# DRS4.net
KiCad netlist of a schematic drawn in Altium Designer
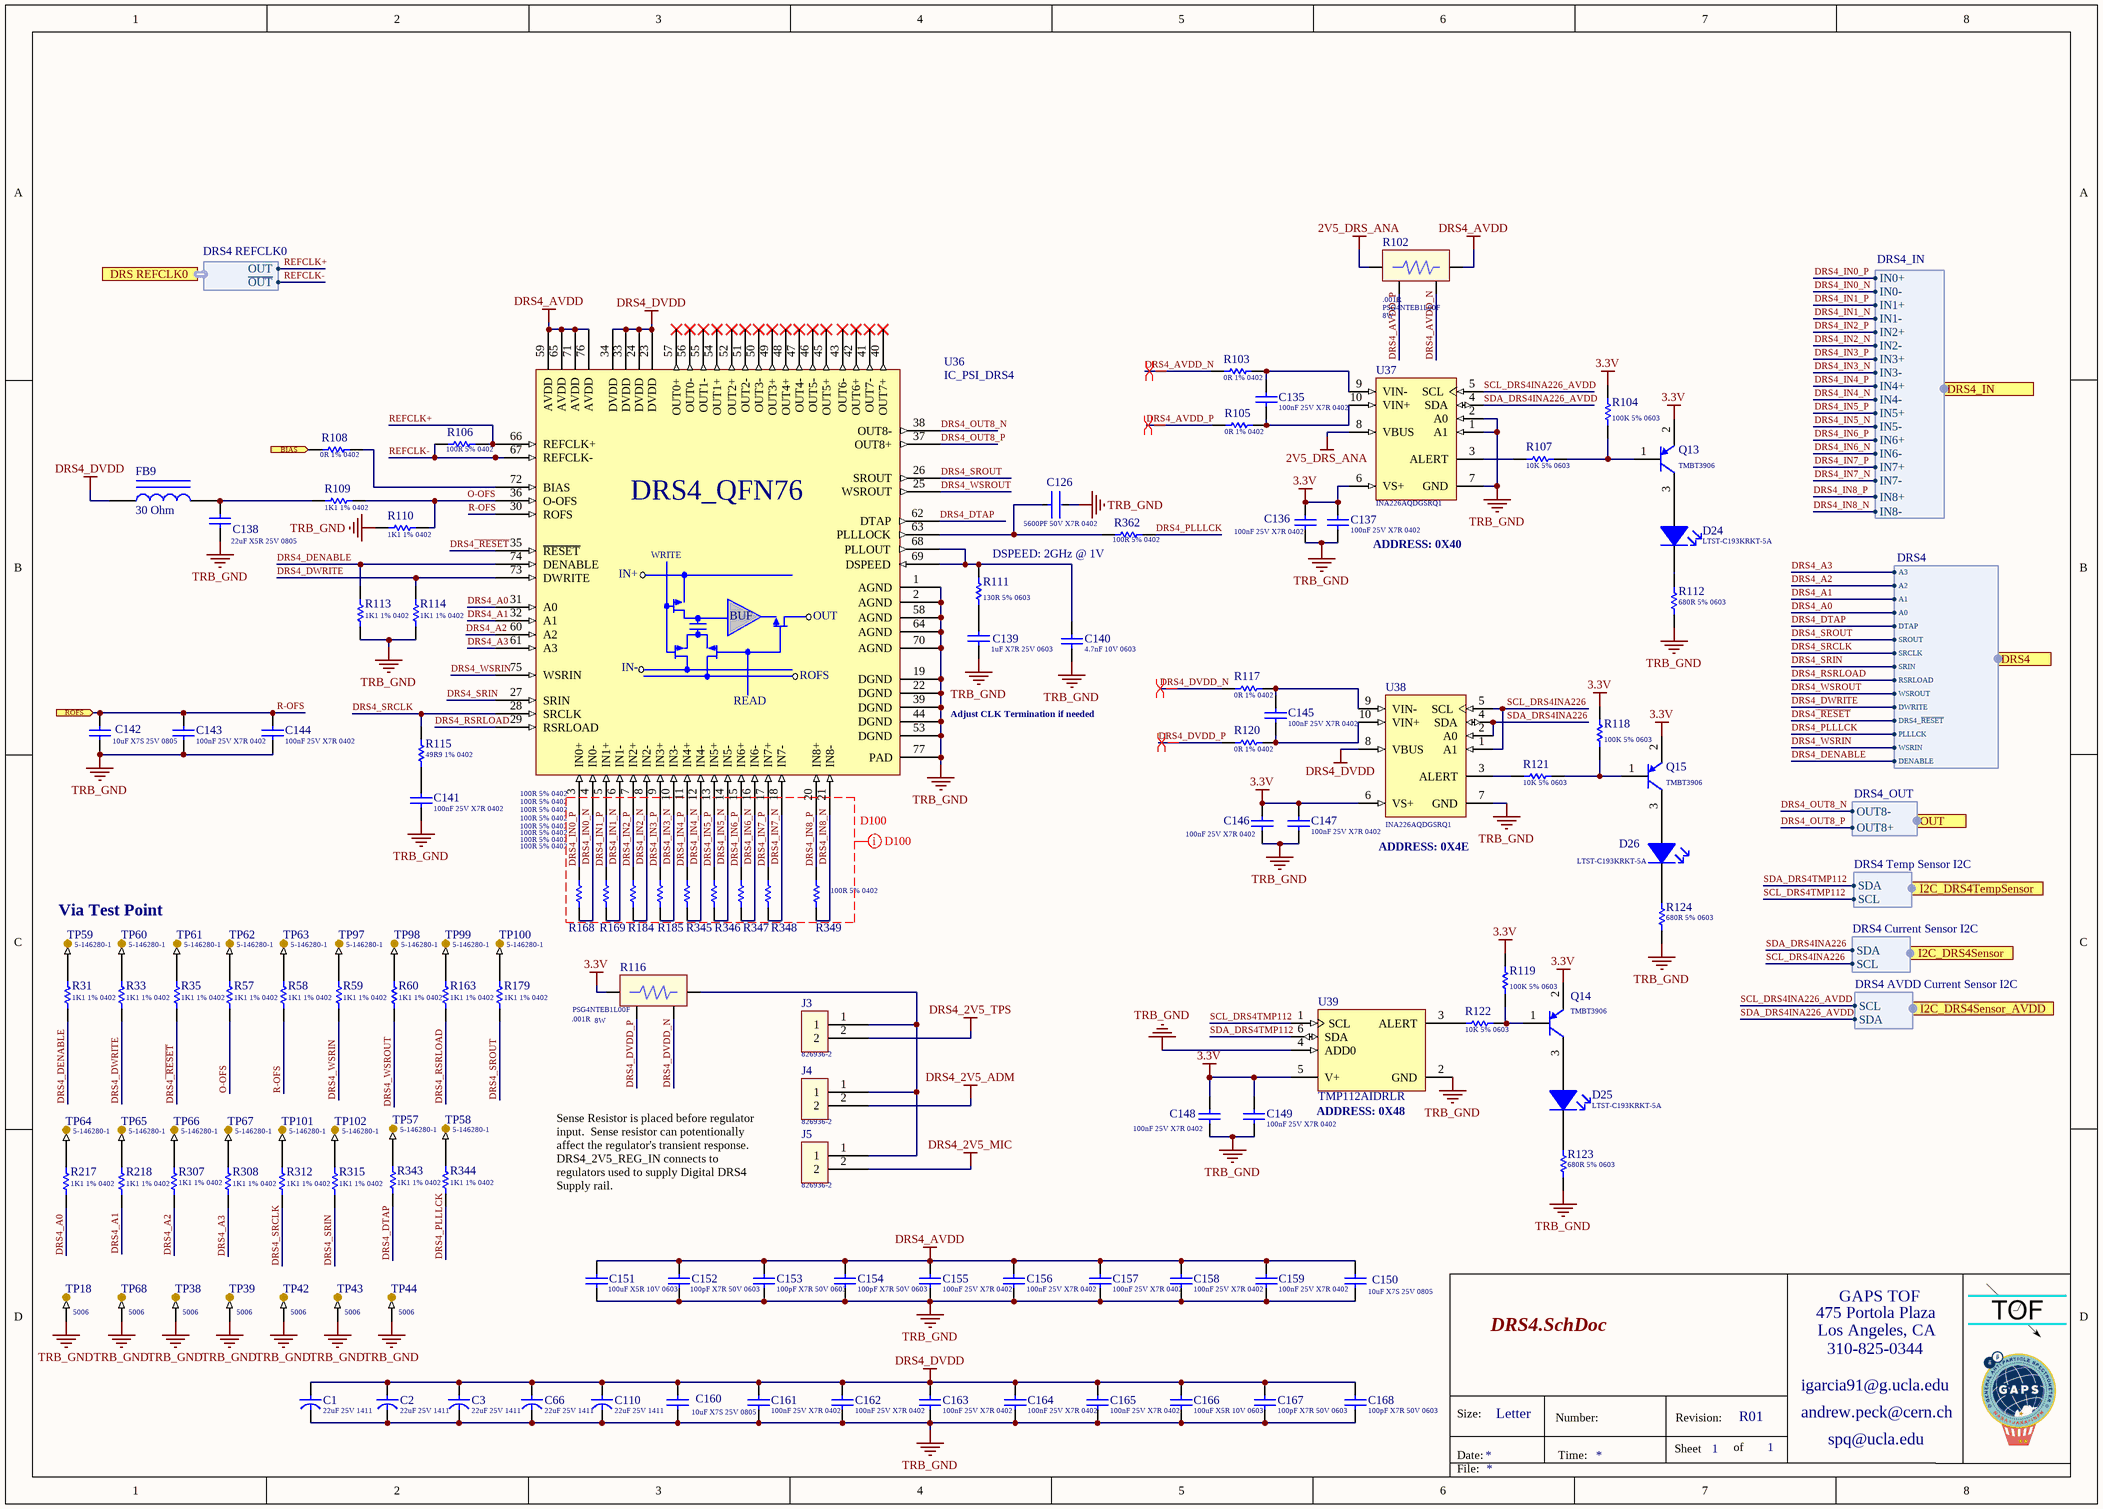
[diagram p0: DRS4.SchDoc]

(export (version "E")
  (design (tool "Eeschema 10.0.6"))
  (components
    (comp (ref "C1")
      (value "Cap_Kemet_T521B226M025ATE100_22uF")
      (footprint "Cap_Kemet_T521B226M025ATE100_22uF")
      (description "Tantalum Capacitors - Polymer SMD 25V 22uF 1311 20% ESR=100mOhms")
      (fields (field (name "CAPACITANCE") "22uF 25V 1411"))
      (libsource (lib "Cap_Kemet_T521B226M025ATE100_22uF") (part "Cap_Kemet_T521B226M025ATE100_22uF"))
    )
    (comp (ref "C2")
      (value "Cap_Kemet_T521B226M025ATE100_22uF")
      (footprint "Cap_Kemet_T521B226M025ATE100_22uF")
      (description "Tantalum Capacitors - Polymer SMD 25V 22uF 1311 20% ESR=100mOhms")
      (fields (field (name "CAPACITANCE") "22uF 25V 1411"))
      (libsource (lib "Cap_Kemet_T521B226M025ATE100_22uF") (part "Cap_Kemet_T521B226M025ATE100_22uF"))
    )
    (comp (ref "C3")
      (value "Cap_Kemet_T521B226M025ATE100_22uF")
      (footprint "Cap_Kemet_T521B226M025ATE100_22uF")
      (description "Tantalum Capacitors - Polymer SMD 25V 22uF 1311 20% ESR=100mOhms")
      (fields (field (name "CAPACITANCE") "22uF 25V 1411"))
      (libsource (lib "Cap_Kemet_T521B226M025ATE100_22uF") (part "Cap_Kemet_T521B226M025ATE100_22uF"))
    )
    (comp (ref "C66")
      (value "Cap_Kemet_T521B226M025ATE100_22uF")
      (footprint "Cap_Kemet_T521B226M025ATE100_22uF")
      (description "Tantalum Capacitors - Polymer SMD 25V 22uF 1311 20% ESR=100mOhms")
      (fields (field (name "CAPACITANCE") "22uF 25V 1411"))
      (libsource (lib "Cap_Kemet_T521B226M025ATE100_22uF") (part "Cap_Kemet_T521B226M025ATE100_22uF"))
    )
    (comp (ref "C110")
      (value "Cap_Kemet_T521B226M025ATE100_22uF")
      (footprint "Cap_Kemet_T521B226M025ATE100_22uF")
      (description "Tantalum Capacitors - Polymer SMD 25V 22uF 1311 20% ESR=100mOhms")
      (fields (field (name "CAPACITANCE") "22uF 25V 1411"))
      (libsource (lib "Cap_Kemet_T521B226M025ATE100_22uF") (part "Cap_Kemet_T521B226M025ATE100_22uF"))
    )
    (comp (ref "C126")
      (value "5600PF 50V X7R 0402")
      (footprint "FP-C0402-BB-MFG")
      (description "CAP CER 5600PF 50V X7R 0402\r\nC0402C562K5RACTU")
      (fields (field (name "TOLERANCE") "0.1") (field (name "MANUFACTURER") "Kemet"))
      (libsource (lib "Altium Content Vault") (part "b4654b650e69147ec39a6b967a45e02"))
    )
    (comp (ref "C135")
      (value "Cap_Taiyo_Yuden_TMK105B7104KV-FR_100nF")
      (footprint "Cap_Taiyo_Yuden_TMK105B7104KV-FR_100nF")
      (description "CAP CER 100nF 25V X7R 0402")
      (fields (field (name "CAPACITANCE") "100nF 25V X7R 0402"))
      (libsource (lib "Cap_Taiyo_Yuden_TMK105B7104KV-FR_100nF") (part "Cap_Taiyo_Yuden_TMK105B7104KV-FR_100nF"))
    )
    (comp (ref "C136")
      (value "Cap_Taiyo_Yuden_TMK105B7104KV-FR_100nF")
      (footprint "Cap_Taiyo_Yuden_TMK105B7104KV-FR_100nF")
      (description "CAP CER 100nF 25V X7R 0402")
      (fields (field (name "CAPACITANCE") "100nF 25V X7R 0402"))
      (libsource (lib "Cap_Taiyo_Yuden_TMK105B7104KV-FR_100nF") (part "Cap_Taiyo_Yuden_TMK105B7104KV-FR_100nF"))
    )
    (comp (ref "C137")
      (value "Cap_Taiyo_Yuden_TMK105B7104KV-FR_100nF")
      (footprint "Cap_Taiyo_Yuden_TMK105B7104KV-FR_100nF")
      (description "CAP CER 100nF 25V X7R 0402")
      (fields (field (name "CAPACITANCE") "100nF 25V X7R 0402"))
      (libsource (lib "Cap_Taiyo_Yuden_TMK105B7104KV-FR_100nF") (part "Cap_Taiyo_Yuden_TMK105B7104KV-FR_100nF"))
    )
    (comp (ref "C138")
      (value "Cap_Murata_GRT21BR61E226ME13L_22uF")
      (footprint "Cap_Murata_GRT21BR61E226ME13L_22uF")
      (description "CAP CER 22uF 25V X5R 0805")
      (fields (field (name "CAPACITANCE") "22uF X5R 25V 0805"))
      (libsource (lib "Cap_Murata_GRT21BR61E226ME13L_22uF") (part "Cap_Murata_GRT21BR61E226ME13L_22uF"))
    )
    (comp (ref "C139")
      (value "Cap_Murata_GCJ188R71E105KA01J_1uF")
      (footprint "Cap_Murata_GCJ188R71E105KA01J_1uF")
      (description "CAP CER 1uF 25V X7R 0603")
      (fields (field (name "CAPACITANCE") "1uF X7R 25V 0603"))
      (libsource (lib "Cap_Murata_GCJ188R71E105KA01J_1uF") (part "Cap_Murata_GCJ188R71E105KA01J_1uF"))
    )
    (comp (ref "C140")
      (value "4.7nF 10V 0603")
      (footprint "CAPC0603(1608)100_L")
      (description "CAP 4.7nF 10V ±10% 0603 (1608 Metric) Thickness 1mm SMD")
      (fields (field (name "TOLERANCE") "Â±10%"))
      (libsource (lib "Altium Content Vault") (part "CAP"))
    )
    (comp (ref "C141")
      (value "Cap_Taiyo_Yuden_TMK105B7104KV-FR_100nF")
      (footprint "Cap_Taiyo_Yuden_TMK105B7104KV-FR_100nF")
      (description "CAP CER 100nF 25V X7R 0402")
      (fields (field (name "CAPACITANCE") "100nF 25V X7R 0402"))
      (libsource (lib "Cap_Taiyo_Yuden_TMK105B7104KV-FR_100nF") (part "Cap_Taiyo_Yuden_TMK105B7104KV-FR_100nF"))
    )
    (comp (ref "C142")
      (value "Cap_Murata_ GRM21BC71E106ME11L_10uF")
      (footprint "Cap_Murata_ GRM21BC71E106ME11L_10uF")
      (description "CAP CER 10uF 25V X7R 0805")
      (fields (field (name "CAPACITANCE") "10uF X7S 25V 0805"))
      (libsource (lib "Cap_Murata_ GRM21BC71E106ME11L_10uF") (part "Cap_Murata_ GRM21BC71E106ME11L_10uF"))
    )
    (comp (ref "C143")
      (value "Cap_Taiyo_Yuden_TMK105B7104KV-FR_100nF")
      (footprint "Cap_Taiyo_Yuden_TMK105B7104KV-FR_100nF")
      (description "CAP CER 100nF 25V X7R 0402")
      (fields (field (name "CAPACITANCE") "100nF 25V X7R 0402"))
      (libsource (lib "Cap_Taiyo_Yuden_TMK105B7104KV-FR_100nF") (part "Cap_Taiyo_Yuden_TMK105B7104KV-FR_100nF"))
    )
    (comp (ref "C144")
      (value "Cap_Taiyo_Yuden_TMK105B7104KV-FR_100nF")
      (footprint "Cap_Taiyo_Yuden_TMK105B7104KV-FR_100nF")
      (description "CAP CER 100nF 25V X7R 0402")
      (fields (field (name "CAPACITANCE") "100nF 25V X7R 0402"))
      (libsource (lib "Cap_Taiyo_Yuden_TMK105B7104KV-FR_100nF") (part "Cap_Taiyo_Yuden_TMK105B7104KV-FR_100nF"))
    )
    (comp (ref "C145")
      (value "Cap_Taiyo_Yuden_TMK105B7104KV-FR_100nF")
      (footprint "Cap_Taiyo_Yuden_TMK105B7104KV-FR_100nF")
      (description "CAP CER 100nF 25V X7R 0402")
      (fields (field (name "CAPACITANCE") "100nF 25V X7R 0402"))
      (libsource (lib "Cap_Taiyo_Yuden_TMK105B7104KV-FR_100nF") (part "Cap_Taiyo_Yuden_TMK105B7104KV-FR_100nF"))
    )
    (comp (ref "C146")
      (value "Cap_Taiyo_Yuden_TMK105B7104KV-FR_100nF")
      (footprint "Cap_Taiyo_Yuden_TMK105B7104KV-FR_100nF")
      (description "CAP CER 100nF 25V X7R 0402")
      (fields (field (name "CAPACITANCE") "100nF 25V X7R 0402"))
      (libsource (lib "Cap_Taiyo_Yuden_TMK105B7104KV-FR_100nF") (part "Cap_Taiyo_Yuden_TMK105B7104KV-FR_100nF"))
    )
    (comp (ref "C147")
      (value "Cap_Taiyo_Yuden_TMK105B7104KV-FR_100nF")
      (footprint "Cap_Taiyo_Yuden_TMK105B7104KV-FR_100nF")
      (description "CAP CER 100nF 25V X7R 0402")
      (fields (field (name "CAPACITANCE") "100nF 25V X7R 0402"))
      (libsource (lib "Cap_Taiyo_Yuden_TMK105B7104KV-FR_100nF") (part "Cap_Taiyo_Yuden_TMK105B7104KV-FR_100nF"))
    )
    (comp (ref "C148")
      (value "Cap_Taiyo_Yuden_TMK105B7104KV-FR_100nF")
      (footprint "Cap_Taiyo_Yuden_TMK105B7104KV-FR_100nF")
      (description "CAP CER 100nF 25V X7R 0402")
      (fields (field (name "CAPACITANCE") "100nF 25V X7R 0402"))
      (libsource (lib "Cap_Taiyo_Yuden_TMK105B7104KV-FR_100nF") (part "Cap_Taiyo_Yuden_TMK105B7104KV-FR_100nF"))
    )
    (comp (ref "C149")
      (value "Cap_Taiyo_Yuden_TMK105B7104KV-FR_100nF")
      (footprint "Cap_Taiyo_Yuden_TMK105B7104KV-FR_100nF")
      (description "CAP CER 100nF 25V X7R 0402")
      (fields (field (name "CAPACITANCE") "100nF 25V X7R 0402"))
      (libsource (lib "Cap_Taiyo_Yuden_TMK105B7104KV-FR_100nF") (part "Cap_Taiyo_Yuden_TMK105B7104KV-FR_100nF"))
    )
    (comp (ref "C150")
      (value "Cap_Murata_ GRM21BC71E106ME11L_10uF")
      (footprint "Cap_Murata_ GRM21BC71E106ME11L_10uF")
      (description "CAP CER 10uF 25V X7R 0805")
      (fields (field (name "CAPACITANCE") "10uF X7S 25V 0805"))
      (libsource (lib "Cap_Murata_ GRM21BC71E106ME11L_10uF") (part "Cap_Murata_ GRM21BC71E106ME11L_10uF"))
    )
    (comp (ref "C151")
      (value "Cap_Murata_GRM31CR61A107ME05L_100uF")
      (footprint "Cap_Murata_GRM31CR61A107ME05L_100uF")
      (description "CAP CER 100uF 25V X5R 0603")
      (fields (field (name "CAPACITANCE") "100uF X5R 10V 0603"))
      (libsource (lib "Cap_Murata_GRM31CR61A107ME05L_100uF") (part "Cap_Murata_GRM31CR61A107ME05L_100uF"))
    )
    (comp (ref "C152")
      (value "Cap_Kemet_C0603C101J5RACTU_100pF")
      (footprint "Cap_Kemet_C0603C101J5RACTU_100pF")
      (description "CAP CER 100pF 50V X7R 0603")
      (fields (field (name "CAPACITANCE") "100pF X7R 50V 0603"))
      (libsource (lib "Cap_Kemet_C0603C101J5RACTU_100pF") (part "Cap_Kemet_C0603C101J5RACTU_100pF"))
    )
    (comp (ref "C153")
      (value "Cap_Kemet_C0603C101J5RACTU_100pF")
      (footprint "Cap_Kemet_C0603C101J5RACTU_100pF")
      (description "CAP CER 100pF 50V X7R 0603")
      (fields (field (name "CAPACITANCE") "100pF X7R 50V 0603"))
      (libsource (lib "Cap_Kemet_C0603C101J5RACTU_100pF") (part "Cap_Kemet_C0603C101J5RACTU_100pF"))
    )
    (comp (ref "C154")
      (value "Cap_Kemet_C0603C101J5RACTU_100pF")
      (footprint "Cap_Kemet_C0603C101J5RACTU_100pF")
      (description "CAP CER 100pF 50V X7R 0603")
      (fields (field (name "CAPACITANCE") "100pF X7R 50V 0603"))
      (libsource (lib "Cap_Kemet_C0603C101J5RACTU_100pF") (part "Cap_Kemet_C0603C101J5RACTU_100pF"))
    )
    (comp (ref "C155")
      (value "Cap_Taiyo_Yuden_TMK105B7104KV-FR_100nF")
      (footprint "Cap_Taiyo_Yuden_TMK105B7104KV-FR_100nF")
      (description "CAP CER 100nF 25V X7R 0402")
      (fields (field (name "CAPACITANCE") "100nF 25V X7R 0402"))
      (libsource (lib "Cap_Taiyo_Yuden_TMK105B7104KV-FR_100nF") (part "Cap_Taiyo_Yuden_TMK105B7104KV-FR_100nF"))
    )
    (comp (ref "C156")
      (value "Cap_Taiyo_Yuden_TMK105B7104KV-FR_100nF")
      (footprint "Cap_Taiyo_Yuden_TMK105B7104KV-FR_100nF")
      (description "CAP CER 100nF 25V X7R 0402")
      (fields (field (name "CAPACITANCE") "100nF 25V X7R 0402"))
      (libsource (lib "Cap_Taiyo_Yuden_TMK105B7104KV-FR_100nF") (part "Cap_Taiyo_Yuden_TMK105B7104KV-FR_100nF"))
    )
    (comp (ref "C157")
      (value "Cap_Taiyo_Yuden_TMK105B7104KV-FR_100nF")
      (footprint "Cap_Taiyo_Yuden_TMK105B7104KV-FR_100nF")
      (description "CAP CER 100nF 25V X7R 0402")
      (fields (field (name "CAPACITANCE") "100nF 25V X7R 0402"))
      (libsource (lib "Cap_Taiyo_Yuden_TMK105B7104KV-FR_100nF") (part "Cap_Taiyo_Yuden_TMK105B7104KV-FR_100nF"))
    )
    (comp (ref "C158")
      (value "Cap_Taiyo_Yuden_TMK105B7104KV-FR_100nF")
      (footprint "Cap_Taiyo_Yuden_TMK105B7104KV-FR_100nF")
      (description "CAP CER 100nF 25V X7R 0402")
      (fields (field (name "CAPACITANCE") "100nF 25V X7R 0402"))
      (libsource (lib "Cap_Taiyo_Yuden_TMK105B7104KV-FR_100nF") (part "Cap_Taiyo_Yuden_TMK105B7104KV-FR_100nF"))
    )
    (comp (ref "C159")
      (value "Cap_Taiyo_Yuden_TMK105B7104KV-FR_100nF")
      (footprint "Cap_Taiyo_Yuden_TMK105B7104KV-FR_100nF")
      (description "CAP CER 100nF 25V X7R 0402")
      (fields (field (name "CAPACITANCE") "100nF 25V X7R 0402"))
      (libsource (lib "Cap_Taiyo_Yuden_TMK105B7104KV-FR_100nF") (part "Cap_Taiyo_Yuden_TMK105B7104KV-FR_100nF"))
    )
    (comp (ref "C160")
      (value "Cap_Murata_ GRM21BC71E106ME11L_10uF")
      (footprint "Cap_Murata_ GRM21BC71E106ME11L_10uF")
      (description "CAP CER 10uF 25V X7R 0805")
      (fields (field (name "CAPACITANCE") "10uF X7S 25V 0805"))
      (libsource (lib "Cap_Murata_ GRM21BC71E106ME11L_10uF") (part "Cap_Murata_ GRM21BC71E106ME11L_10uF"))
    )
    (comp (ref "C161")
      (value "Cap_Taiyo_Yuden_TMK105B7104KV-FR_100nF")
      (footprint "Cap_Taiyo_Yuden_TMK105B7104KV-FR_100nF")
      (description "CAP CER 100nF 25V X7R 0402")
      (fields (field (name "CAPACITANCE") "100nF 25V X7R 0402"))
      (libsource (lib "Cap_Taiyo_Yuden_TMK105B7104KV-FR_100nF") (part "Cap_Taiyo_Yuden_TMK105B7104KV-FR_100nF"))
    )
    (comp (ref "C162")
      (value "Cap_Taiyo_Yuden_TMK105B7104KV-FR_100nF")
      (footprint "Cap_Taiyo_Yuden_TMK105B7104KV-FR_100nF")
      (description "CAP CER 100nF 25V X7R 0402")
      (fields (field (name "CAPACITANCE") "100nF 25V X7R 0402"))
      (libsource (lib "Cap_Taiyo_Yuden_TMK105B7104KV-FR_100nF") (part "Cap_Taiyo_Yuden_TMK105B7104KV-FR_100nF"))
    )
    (comp (ref "C163")
      (value "Cap_Taiyo_Yuden_TMK105B7104KV-FR_100nF")
      (footprint "Cap_Taiyo_Yuden_TMK105B7104KV-FR_100nF")
      (description "CAP CER 100nF 25V X7R 0402")
      (fields (field (name "CAPACITANCE") "100nF 25V X7R 0402"))
      (libsource (lib "Cap_Taiyo_Yuden_TMK105B7104KV-FR_100nF") (part "Cap_Taiyo_Yuden_TMK105B7104KV-FR_100nF"))
    )
    (comp (ref "C164")
      (value "Cap_Taiyo_Yuden_TMK105B7104KV-FR_100nF")
      (footprint "Cap_Taiyo_Yuden_TMK105B7104KV-FR_100nF")
      (description "CAP CER 100nF 25V X7R 0402")
      (fields (field (name "CAPACITANCE") "100nF 25V X7R 0402"))
      (libsource (lib "Cap_Taiyo_Yuden_TMK105B7104KV-FR_100nF") (part "Cap_Taiyo_Yuden_TMK105B7104KV-FR_100nF"))
    )
    (comp (ref "C165")
      (value "Cap_Taiyo_Yuden_TMK105B7104KV-FR_100nF")
      (footprint "Cap_Taiyo_Yuden_TMK105B7104KV-FR_100nF")
      (description "CAP CER 100nF 25V X7R 0402")
      (fields (field (name "CAPACITANCE") "100nF 25V X7R 0402"))
      (libsource (lib "Cap_Taiyo_Yuden_TMK105B7104KV-FR_100nF") (part "Cap_Taiyo_Yuden_TMK105B7104KV-FR_100nF"))
    )
    (comp (ref "C166")
      (value "Cap_Murata_GRM31CR61A107ME05L_100uF")
      (footprint "Cap_Murata_GRM31CR61A107ME05L_100uF")
      (description "CAP CER 100uF 25V X5R 0603")
      (fields (field (name "CAPACITANCE") "100uF X5R 10V 0603"))
      (libsource (lib "Cap_Murata_GRM31CR61A107ME05L_100uF") (part "Cap_Murata_GRM31CR61A107ME05L_100uF"))
    )
    (comp (ref "C167")
      (value "Cap_Kemet_C0603C101J5RACTU_100pF")
      (footprint "Cap_Kemet_C0603C101J5RACTU_100pF")
      (description "CAP CER 100pF 50V X7R 0603")
      (fields (field (name "CAPACITANCE") "100pF X7R 50V 0603"))
      (libsource (lib "Cap_Kemet_C0603C101J5RACTU_100pF") (part "Cap_Kemet_C0603C101J5RACTU_100pF"))
    )
    (comp (ref "C168")
      (value "Cap_Kemet_C0603C101J5RACTU_100pF")
      (footprint "Cap_Kemet_C0603C101J5RACTU_100pF")
      (description "CAP CER 100pF 50V X7R 0603")
      (fields (field (name "CAPACITANCE") "100pF X7R 50V 0603"))
      (libsource (lib "Cap_Kemet_C0603C101J5RACTU_100pF") (part "Cap_Kemet_C0603C101J5RACTU_100pF"))
    )
    (comp (ref "D24")
      (value "LTST-C193KRKT-5A")
      (footprint "Led_Lite-On_LTST-C193KGKT-5A_Red")
      (description "Standard LEDs - SMD Red 470nm 28mcd 20mA")
      (fields (field (name "SERIES") "LTST-C193KRKT-5A"))
      (libsource (lib "Led_Lite-On_LTST-C193KGKT-5A_Red") (part "Led_Lite-On_LTST-C193KGKT-5A_Red"))
    )
    (comp (ref "D25")
      (value "LTST-C193KRKT-5A")
      (footprint "Led_Lite-On_LTST-C193KGKT-5A_Red")
      (description "Standard LEDs - SMD Red 470nm 28mcd 20mA")
      (fields (field (name "SERIES") "LTST-C193KRKT-5A"))
      (libsource (lib "Led_Lite-On_LTST-C193KGKT-5A_Red") (part "Led_Lite-On_LTST-C193KGKT-5A_Red"))
    )
    (comp (ref "D26")
      (value "LTST-C193KRKT-5A")
      (footprint "Led_Lite-On_LTST-C193KGKT-5A_Red")
      (description "Standard LEDs - SMD Red 470nm 28mcd 20mA")
      (fields (field (name "SERIES") "LTST-C193KRKT-5A"))
      (libsource (lib "Led_Lite-On_LTST-C193KGKT-5A_Red") (part "Led_Lite-On_LTST-C193KGKT-5A_Red"))
    )
    (comp (ref "FB9")
      (value "30 Ohm")
      (footprint "Feb_MURATA_BLM15AX300SZ1D_30")
      (description "Feb SMD 30 OHM 25% 3/4W 0402")
      (libsource (lib "Feb_MURATA_BLM15AX300SZ1D_30") (part "Feb_MURATA_BLM15AX300SZ1D_30"))
    )
    (comp (ref "J3")
      (value "Header_TE_Connectivity_826936-2_2POS_5A")
      (footprint "Header_TE_Connectivity_826936-2_2POS_5A")
      (description "Headers & Wire Housings 2P SINGLE ROW 5A")
      (fields (field (name "SERIES") "826936-2"))
      (libsource (lib "Header_TE_Connectivity_826936-2_2POS_5A") (part "Header_TE_Connectivity_826936-2_2POS_5A"))
    )
    (comp (ref "J4")
      (value "Header_TE_Connectivity_826936-2_2POS_5A")
      (footprint "Header_TE_Connectivity_826936-2_2POS_5A")
      (description "Headers & Wire Housings 2P SINGLE ROW 5A")
      (fields (field (name "SERIES") "826936-2"))
      (libsource (lib "Header_TE_Connectivity_826936-2_2POS_5A") (part "Header_TE_Connectivity_826936-2_2POS_5A"))
    )
    (comp (ref "J5")
      (value "Header_TE_Connectivity_826936-2_2POS_5A")
      (footprint "Header_TE_Connectivity_826936-2_2POS_5A")
      (description "Headers & Wire Housings 2P SINGLE ROW 5A")
      (fields (field (name "SERIES") "826936-2"))
      (libsource (lib "Header_TE_Connectivity_826936-2_2POS_5A") (part "Header_TE_Connectivity_826936-2_2POS_5A"))
    )
    (comp (ref "Q13")
      (value "BJT_PNP_Toshiba_TMBT3906")
      (footprint "BJT_PNP_Toshiba_TMBT3906")
      (description "Bipolar Transistors - BJT Transistor for Low Freq. Amplification")
      (fields (field (name "SERIES") "TMBT3906"))
      (libsource (lib "BJT_PNP_Toshiba_TMBT3906") (part "BJT_PNP_Toshiba_TMBT3906"))
    )
    (comp (ref "Q14")
      (value "BJT_PNP_Toshiba_TMBT3906")
      (footprint "BJT_PNP_Toshiba_TMBT3906")
      (description "Bipolar Transistors - BJT Transistor for Low Freq. Amplification")
      (fields (field (name "SERIES") "TMBT3906"))
      (libsource (lib "BJT_PNP_Toshiba_TMBT3906") (part "BJT_PNP_Toshiba_TMBT3906"))
    )
    (comp (ref "Q15")
      (value "BJT_PNP_Toshiba_TMBT3906")
      (footprint "BJT_PNP_Toshiba_TMBT3906")
      (description "Bipolar Transistors - BJT Transistor for Low Freq. Amplification")
      (fields (field (name "SERIES") "TMBT3906"))
      (libsource (lib "BJT_PNP_Toshiba_TMBT3906") (part "BJT_PNP_Toshiba_TMBT3906"))
    )
    (comp (ref "R31")
      (value "1K1 1% 0402")
      (footprint "RESC0402(1005)_L")
      (description "1K1 0.063W 1% 0402 (1005 Metric)  SMD")
      (fields (field (name "POWER") "0.063 W") (field (name "TOLERANCE") "1 %"))
      (libsource (lib "Altium Content Vault") (part "RES"))
    )
    (comp (ref "R33")
      (value "1K1 1% 0402")
      (footprint "RESC0402(1005)_L")
      (description "1K1 0.063W 1% 0402 (1005 Metric)  SMD")
      (fields (field (name "POWER") "0.063 W") (field (name "TOLERANCE") "1 %"))
      (libsource (lib "Altium Content Vault") (part "RES"))
    )
    (comp (ref "R35")
      (value "1K1 1% 0402")
      (footprint "RESC0402(1005)_L")
      (description "1K1 0.063W 1% 0402 (1005 Metric)  SMD")
      (fields (field (name "POWER") "0.063 W") (field (name "TOLERANCE") "1 %"))
      (libsource (lib "Altium Content Vault") (part "RES"))
    )
    (comp (ref "R57")
      (value "1K1 1% 0402")
      (footprint "RESC0402(1005)_L")
      (description "1K1 0.063W 1% 0402 (1005 Metric)  SMD")
      (fields (field (name "POWER") "0.063 W") (field (name "TOLERANCE") "1 %"))
      (libsource (lib "Altium Content Vault") (part "RES"))
    )
    (comp (ref "R58")
      (value "1K1 1% 0402")
      (footprint "RESC0402(1005)_L")
      (description "1K1 0.063W 1% 0402 (1005 Metric)  SMD")
      (fields (field (name "POWER") "0.063 W") (field (name "TOLERANCE") "1 %"))
      (libsource (lib "Altium Content Vault") (part "RES"))
    )
    (comp (ref "R59")
      (value "1K1 1% 0402")
      (footprint "RESC0402(1005)_L")
      (description "1K1 0.063W 1% 0402 (1005 Metric)  SMD")
      (fields (field (name "POWER") "0.063 W") (field (name "TOLERANCE") "1 %"))
      (libsource (lib "Altium Content Vault") (part "RES"))
    )
    (comp (ref "R60")
      (value "1K1 1% 0402")
      (footprint "RESC0402(1005)_L")
      (description "1K1 0.063W 1% 0402 (1005 Metric)  SMD")
      (fields (field (name "POWER") "0.063 W") (field (name "TOLERANCE") "1 %"))
      (libsource (lib "Altium Content Vault") (part "RES"))
    )
    (comp (ref "R102")
      (value "SRes_KOA_PSG4NTEB1L00F_1mOhm")
      (footprint "SRes_KOA_PSG4NTEB1L00F_1mOhm")
      (description "Current Sense Resistors - SMD 1mOhm 8W 1% 50ppm AEC-Q200 Power Shunt")
      (fields
        (field (name "RESISTANCE") ".001R")
        (field (name "SERIES") "PSG4NTEB1L00F")
        (field (name "PARAMETER 1") "8W")
      )
      (libsource (lib "SRes_KOA_PSG4NTEB1L00F_1mOhm") (part "SRes_KOA_PSG4NTEB1L00F_1mOhm"))
    )
    (comp (ref "R103")
      (value "Res_Vishay_CRCW04020000Z0EDC_0_Ohm")
      (footprint "Res_Vishay_CRCW04020000Z0EDC_0_Ohm")
      (description "0R 0.062W 1% 0402 (1005 Metric)  SMD")
      (fields (field (name "RESISTANCE") "0R 1% 0402"))
      (libsource (lib "Res_Vishay_CRCW04020000Z0EDC_0_Ohm") (part "Res_Vishay_CRCW04020000Z0EDC_0_Ohm"))
    )
    (comp (ref "R104")
      (value "100K 5% 0603")
      (footprint "RESC0603(1608)_N")
      (description "100K 0.1W 5% 0603 (1608 Metric)  SMD")
      (fields (field (name "TOLERANCE") "5 %") (field (name "POWER") "0.1 W"))
      (libsource (lib "Altium Content Vault") (part "RES"))
    )
    (comp (ref "R105")
      (value "Res_Vishay_CRCW04020000Z0EDC_0_Ohm")
      (footprint "Res_Vishay_CRCW04020000Z0EDC_0_Ohm")
      (description "0R 0.062W 1% 0402 (1005 Metric)  SMD")
      (fields (field (name "RESISTANCE") "0R 1% 0402"))
      (libsource (lib "Res_Vishay_CRCW04020000Z0EDC_0_Ohm") (part "Res_Vishay_CRCW04020000Z0EDC_0_Ohm"))
    )
    (comp (ref "R106")
      (value "100R 5% 0402")
      (footprint "RESC0402(1005)_L")
      (description "100R 0.063W 5% 0402 (1005 Metric)  SMD")
      (fields (field (name "TOLERANCE") "5 %") (field (name "POWER") "0.063 W"))
      (libsource (lib "Altium Content Vault") (part "RES"))
    )
    (comp (ref "R107")
      (value "10K 5% 0603")
      (footprint "RESC0603(1608)_L")
      (description "10K 0.1W 5% 0603 (1608 Metric)  SMD")
      (fields (field (name "TOLERANCE") "5 %") (field (name "POWER") "0.1 W"))
      (libsource (lib "Altium Content Vault") (part "RES"))
    )
    (comp (ref "R108")
      (value "Res_Vishay_CRCW04020000Z0EDC_0_Ohm")
      (footprint "Res_Vishay_CRCW04020000Z0EDC_0_Ohm")
      (description "0R 0.062W 1% 0402 (1005 Metric)  SMD")
      (fields (field (name "RESISTANCE") "0R 1% 0402"))
      (libsource (lib "Res_Vishay_CRCW04020000Z0EDC_0_Ohm") (part "Res_Vishay_CRCW04020000Z0EDC_0_Ohm"))
    )
    (comp (ref "R109")
      (value "1K1 1% 0402")
      (footprint "RESC0402(1005)_L")
      (description "1K1 0.063W 1% 0402 (1005 Metric)  SMD")
      (fields (field (name "POWER") "0.063 W") (field (name "TOLERANCE") "1 %"))
      (libsource (lib "Altium Content Vault") (part "RES"))
    )
    (comp (ref "R110")
      (value "1K1 1% 0402")
      (footprint "RESC0402(1005)_L")
      (description "1K1 0.063W 1% 0402 (1005 Metric)  SMD")
      (fields (field (name "POWER") "0.063 W") (field (name "TOLERANCE") "1 %"))
      (libsource (lib "Altium Content Vault") (part "RES"))
    )
    (comp (ref "R111")
      (value "130R 5% 0603")
      (footprint "RESC0603(1608)_L")
      (description "130R 0.1W 5% 0603 (1608 Metric)  SMD")
      (fields (field (name "TOLERANCE") "5 %") (field (name "POWER") "0.1 W"))
      (libsource (lib "Altium Content Vault") (part "RES"))
    )
    (comp (ref "R112")
      (value "680R 5% 0603")
      (footprint "RESC0603(1608)_L")
      (description "680R 0.1W 5% 0603 (1608 Metric)  SMD")
      (fields (field (name "TOLERANCE") "5 %") (field (name "POWER") "0.1 W"))
      (libsource (lib "Altium Content Vault") (part "RES"))
    )
    (comp (ref "R113")
      (value "1K1 1% 0402")
      (footprint "RESC0402(1005)_L")
      (description "1K1 0.063W 1% 0402 (1005 Metric)  SMD")
      (fields (field (name "POWER") "0.063 W") (field (name "TOLERANCE") "1 %"))
      (libsource (lib "Altium Content Vault") (part "RES"))
    )
    (comp (ref "R114")
      (value "1K1 1% 0402")
      (footprint "RESC0402(1005)_L")
      (description "1K1 0.063W 1% 0402 (1005 Metric)  SMD")
      (fields (field (name "POWER") "0.063 W") (field (name "TOLERANCE") "1 %"))
      (libsource (lib "Altium Content Vault") (part "RES"))
    )
    (comp (ref "R115")
      (value "49R9 1% 0402")
      (footprint "RESC0402(1005)_L")
      (description "49R9 0.063W 1% 0402 (1005 Metric)  SMD")
      (fields (field (name "POWER") "0.063 W") (field (name "TOLERANCE") "1 %"))
      (libsource (lib "Altium Content Vault") (part "RES"))
    )
    (comp (ref "R116")
      (value "SRes_KOA_PSG4NTEB1L00F_1mOhm")
      (footprint "SRes_KOA_PSG4NTEB1L00F_1mOhm")
      (description "Current Sense Resistors - SMD 1mOhm 8W 1% 50ppm AEC-Q200 Power Shunt")
      (fields
        (field (name "RESISTANCE") ".001R")
        (field (name "SERIES") "PSG4NTEB1L00F")
        (field (name "PARAMETER 1") "8W")
      )
      (libsource (lib "SRes_KOA_PSG4NTEB1L00F_1mOhm") (part "SRes_KOA_PSG4NTEB1L00F_1mOhm"))
    )
    (comp (ref "R117")
      (value "Res_Vishay_CRCW04020000Z0EDC_0_Ohm")
      (footprint "Res_Vishay_CRCW04020000Z0EDC_0_Ohm")
      (description "0R 0.062W 1% 0402 (1005 Metric)  SMD")
      (fields (field (name "RESISTANCE") "0R 1% 0402"))
      (libsource (lib "Res_Vishay_CRCW04020000Z0EDC_0_Ohm") (part "Res_Vishay_CRCW04020000Z0EDC_0_Ohm"))
    )
    (comp (ref "R118")
      (value "100K 5% 0603")
      (footprint "RESC0603(1608)_N")
      (description "100K 0.1W 5% 0603 (1608 Metric)  SMD")
      (fields (field (name "TOLERANCE") "5 %") (field (name "POWER") "0.1 W"))
      (libsource (lib "Altium Content Vault") (part "RES"))
    )
    (comp (ref "R119")
      (value "100K 5% 0603")
      (footprint "RESC0603(1608)_N")
      (description "100K 0.1W 5% 0603 (1608 Metric)  SMD")
      (fields (field (name "TOLERANCE") "5 %") (field (name "POWER") "0.1 W"))
      (libsource (lib "Altium Content Vault") (part "RES"))
    )
    (comp (ref "R120")
      (value "Res_Vishay_CRCW04020000Z0EDC_0_Ohm")
      (footprint "Res_Vishay_CRCW04020000Z0EDC_0_Ohm")
      (description "0R 0.062W 1% 0402 (1005 Metric)  SMD")
      (fields (field (name "RESISTANCE") "0R 1% 0402"))
      (libsource (lib "Res_Vishay_CRCW04020000Z0EDC_0_Ohm") (part "Res_Vishay_CRCW04020000Z0EDC_0_Ohm"))
    )
    (comp (ref "R121")
      (value "10K 5% 0603")
      (footprint "RESC0603(1608)_L")
      (description "10K 0.1W 5% 0603 (1608 Metric)  SMD")
      (fields (field (name "TOLERANCE") "5 %") (field (name "POWER") "0.1 W"))
      (libsource (lib "Altium Content Vault") (part "RES"))
    )
    (comp (ref "R122")
      (value "10K 5% 0603")
      (footprint "RESC0603(1608)_L")
      (description "10K 0.1W 5% 0603 (1608 Metric)  SMD")
      (fields (field (name "TOLERANCE") "5 %") (field (name "POWER") "0.1 W"))
      (libsource (lib "Altium Content Vault") (part "RES"))
    )
    (comp (ref "R123")
      (value "680R 5% 0603")
      (footprint "RESC0603(1608)_L")
      (description "680R 0.1W 5% 0603 (1608 Metric)  SMD")
      (fields (field (name "TOLERANCE") "5 %") (field (name "POWER") "0.1 W"))
      (libsource (lib "Altium Content Vault") (part "RES"))
    )
    (comp (ref "R124")
      (value "680R 5% 0603")
      (footprint "RESC0603(1608)_L")
      (description "680R 0.1W 5% 0603 (1608 Metric)  SMD")
      (fields (field (name "TOLERANCE") "5 %") (field (name "POWER") "0.1 W"))
      (libsource (lib "Altium Content Vault") (part "RES"))
    )
    (comp (ref "R163")
      (value "1K1 1% 0402")
      (footprint "RESC0402(1005)_L")
      (description "1K1 0.063W 1% 0402 (1005 Metric)  SMD")
      (fields (field (name "POWER") "0.063 W") (field (name "TOLERANCE") "1 %"))
      (libsource (lib "Altium Content Vault") (part "RES"))
    )
    (comp (ref "R168")
      (value "100R 5% 0402")
      (footprint "RESC0402(1005)_L")
      (description "100R 0.063W 5% 0402 (1005 Metric)  SMD")
      (fields (field (name "TOLERANCE") "5 %") (field (name "POWER") "0.063 W"))
      (libsource (lib "Altium Content Vault") (part "RES"))
    )
    (comp (ref "R169")
      (value "100R 5% 0402")
      (footprint "RESC0402(1005)_L")
      (description "100R 0.063W 5% 0402 (1005 Metric)  SMD")
      (fields (field (name "TOLERANCE") "5 %") (field (name "POWER") "0.063 W"))
      (libsource (lib "Altium Content Vault") (part "RES"))
    )
    (comp (ref "R179")
      (value "1K1 1% 0402")
      (footprint "RESC0402(1005)_L")
      (description "1K1 0.063W 1% 0402 (1005 Metric)  SMD")
      (fields (field (name "POWER") "0.063 W") (field (name "TOLERANCE") "1 %"))
      (libsource (lib "Altium Content Vault") (part "RES"))
    )
    (comp (ref "R184")
      (value "100R 5% 0402")
      (footprint "RESC0402(1005)_L")
      (description "100R 0.063W 5% 0402 (1005 Metric)  SMD")
      (fields (field (name "TOLERANCE") "5 %") (field (name "POWER") "0.063 W"))
      (libsource (lib "Altium Content Vault") (part "RES"))
    )
    (comp (ref "R185")
      (value "100R 5% 0402")
      (footprint "RESC0402(1005)_L")
      (description "100R 0.063W 5% 0402 (1005 Metric)  SMD")
      (fields (field (name "TOLERANCE") "5 %") (field (name "POWER") "0.063 W"))
      (libsource (lib "Altium Content Vault") (part "RES"))
    )
    (comp (ref "R217")
      (value "1K1 1% 0402")
      (footprint "RESC0402(1005)_L")
      (description "1K1 0.063W 1% 0402 (1005 Metric)  SMD")
      (fields (field (name "POWER") "0.063 W") (field (name "TOLERANCE") "1 %"))
      (libsource (lib "Altium Content Vault") (part "RES"))
    )
    (comp (ref "R218")
      (value "1K1 1% 0402")
      (footprint "RESC0402(1005)_L")
      (description "1K1 0.063W 1% 0402 (1005 Metric)  SMD")
      (fields (field (name "POWER") "0.063 W") (field (name "TOLERANCE") "1 %"))
      (libsource (lib "Altium Content Vault") (part "RES"))
    )
    (comp (ref "R307")
      (value "1K1 1% 0402")
      (footprint "RESC0402(1005)_L")
      (description "1K1 0.063W 1% 0402 (1005 Metric)  SMD")
      (fields (field (name "POWER") "0.063 W") (field (name "TOLERANCE") "1 %"))
      (libsource (lib "Altium Content Vault") (part "RES"))
    )
    (comp (ref "R308")
      (value "1K1 1% 0402")
      (footprint "RESC0402(1005)_L")
      (description "1K1 0.063W 1% 0402 (1005 Metric)  SMD")
      (fields (field (name "POWER") "0.063 W") (field (name "TOLERANCE") "1 %"))
      (libsource (lib "Altium Content Vault") (part "RES"))
    )
    (comp (ref "R312")
      (value "1K1 1% 0402")
      (footprint "RESC0402(1005)_L")
      (description "1K1 0.063W 1% 0402 (1005 Metric)  SMD")
      (fields (field (name "POWER") "0.063 W") (field (name "TOLERANCE") "1 %"))
      (libsource (lib "Altium Content Vault") (part "RES"))
    )
    (comp (ref "R315")
      (value "1K1 1% 0402")
      (footprint "RESC0402(1005)_L")
      (description "1K1 0.063W 1% 0402 (1005 Metric)  SMD")
      (fields (field (name "POWER") "0.063 W") (field (name "TOLERANCE") "1 %"))
      (libsource (lib "Altium Content Vault") (part "RES"))
    )
    (comp (ref "R343")
      (value "1K1 1% 0402")
      (footprint "RESC0402(1005)_L")
      (description "1K1 0.063W 1% 0402 (1005 Metric)  SMD")
      (fields (field (name "POWER") "0.063 W") (field (name "TOLERANCE") "1 %"))
      (libsource (lib "Altium Content Vault") (part "RES"))
    )
    (comp (ref "R344")
      (value "1K1 1% 0402")
      (footprint "RESC0402(1005)_L")
      (description "1K1 0.063W 1% 0402 (1005 Metric)  SMD")
      (fields (field (name "POWER") "0.063 W") (field (name "TOLERANCE") "1 %"))
      (libsource (lib "Altium Content Vault") (part "RES"))
    )
    (comp (ref "R345")
      (value "100R 5% 0402")
      (footprint "RESC0402(1005)_L")
      (description "100R 0.063W 5% 0402 (1005 Metric)  SMD")
      (fields (field (name "TOLERANCE") "5 %") (field (name "POWER") "0.063 W"))
      (libsource (lib "Altium Content Vault") (part "RES"))
    )
    (comp (ref "R346")
      (value "100R 5% 0402")
      (footprint "RESC0402(1005)_L")
      (description "100R 0.063W 5% 0402 (1005 Metric)  SMD")
      (fields (field (name "TOLERANCE") "5 %") (field (name "POWER") "0.063 W"))
      (libsource (lib "Altium Content Vault") (part "RES"))
    )
    (comp (ref "R347")
      (value "100R 5% 0402")
      (footprint "RESC0402(1005)_L")
      (description "100R 0.063W 5% 0402 (1005 Metric)  SMD")
      (fields (field (name "TOLERANCE") "5 %") (field (name "POWER") "0.063 W"))
      (libsource (lib "Altium Content Vault") (part "RES"))
    )
    (comp (ref "R348")
      (value "100R 5% 0402")
      (footprint "RESC0402(1005)_L")
      (description "100R 0.063W 5% 0402 (1005 Metric)  SMD")
      (fields (field (name "TOLERANCE") "5 %") (field (name "POWER") "0.063 W"))
      (libsource (lib "Altium Content Vault") (part "RES"))
    )
    (comp (ref "R349")
      (value "100R 5% 0402")
      (footprint "RESC0402(1005)_L")
      (description "100R 0.063W 5% 0402 (1005 Metric)  SMD")
      (fields (field (name "TOLERANCE") "5 %") (field (name "POWER") "0.063 W"))
      (libsource (lib "Altium Content Vault") (part "RES"))
    )
    (comp (ref "R362")
      (value "100R 5% 0402")
      (footprint "RESC0402(1005)_L")
      (description "100R 0.063W 5% 0402 (1005 Metric)  SMD")
      (fields (field (name "TOLERANCE") "5 %") (field (name "POWER") "0.063 W"))
      (libsource (lib "Altium Content Vault") (part "RES"))
    )
    (comp (ref "TP18")
      (value "TP_Keystone_Electronics_5006")
      (footprint "TP_Keystone_Electronics_5006")
      (description "Circuit Board Hardware - PCB TEST POINT BLK .063")
      (fields (field (name "SERIES") "5006"))
      (libsource (lib "TP_Keystone_Electronics_5006") (part "TP_Keystone_Electronics_5006"))
    )
    (comp (ref "TP38")
      (value "TP_Keystone_Electronics_5006")
      (footprint "TP_Keystone_Electronics_5006")
      (description "Circuit Board Hardware - PCB TEST POINT BLK .063")
      (fields (field (name "SERIES") "5006"))
      (libsource (lib "TP_Keystone_Electronics_5006") (part "TP_Keystone_Electronics_5006"))
    )
    (comp (ref "TP39")
      (value "TP_Keystone_Electronics_5006")
      (footprint "TP_Keystone_Electronics_5006")
      (description "Circuit Board Hardware - PCB TEST POINT BLK .063")
      (fields (field (name "SERIES") "5006"))
      (libsource (lib "TP_Keystone_Electronics_5006") (part "TP_Keystone_Electronics_5006"))
    )
    (comp (ref "TP42")
      (value "TP_Keystone_Electronics_5006")
      (footprint "TP_Keystone_Electronics_5006")
      (description "Circuit Board Hardware - PCB TEST POINT BLK .063")
      (fields (field (name "SERIES") "5006"))
      (libsource (lib "TP_Keystone_Electronics_5006") (part "TP_Keystone_Electronics_5006"))
    )
    (comp (ref "TP43")
      (value "TP_Keystone_Electronics_5006")
      (footprint "TP_Keystone_Electronics_5006")
      (description "Circuit Board Hardware - PCB TEST POINT BLK .063")
      (fields (field (name "SERIES") "5006"))
      (libsource (lib "TP_Keystone_Electronics_5006") (part "TP_Keystone_Electronics_5006"))
    )
    (comp (ref "TP44")
      (value "TP_Keystone_Electronics_5006")
      (footprint "TP_Keystone_Electronics_5006")
      (description "Circuit Board Hardware - PCB TEST POINT BLK .063")
      (fields (field (name "SERIES") "5006"))
      (libsource (lib "TP_Keystone_Electronics_5006") (part "TP_Keystone_Electronics_5006"))
    )
    (comp (ref "TP57")
      (value "TP_TE_Connectivity_5-146280-1_1POS")
      (footprint "TP_TE_Connectivity_5-146280-1_1POS")
      (description "Headers & Wire Housings Unshrouded 1 POS T/H")
      (fields (field (name "SERIES") "5-146280-1"))
      (libsource (lib "TP_TE_Connectivity_5-146280-1_1POS") (part "TP_TE_Connectivity_5-146280-1_1POS"))
    )
    (comp (ref "TP58")
      (value "TP_TE_Connectivity_5-146280-1_1POS")
      (footprint "TP_TE_Connectivity_5-146280-1_1POS")
      (description "Headers & Wire Housings Unshrouded 1 POS T/H")
      (fields (field (name "SERIES") "5-146280-1"))
      (libsource (lib "TP_TE_Connectivity_5-146280-1_1POS") (part "TP_TE_Connectivity_5-146280-1_1POS"))
    )
    (comp (ref "TP59")
      (value "TP_TE_Connectivity_5-146280-1_1POS")
      (footprint "TP_TE_Connectivity_5-146280-1_1POS")
      (description "Headers & Wire Housings Unshrouded 1 POS T/H")
      (fields (field (name "SERIES") "5-146280-1"))
      (libsource (lib "TP_TE_Connectivity_5-146280-1_1POS") (part "TP_TE_Connectivity_5-146280-1_1POS"))
    )
    (comp (ref "TP60")
      (value "TP_TE_Connectivity_5-146280-1_1POS")
      (footprint "TP_TE_Connectivity_5-146280-1_1POS")
      (description "Headers & Wire Housings Unshrouded 1 POS T/H")
      (fields (field (name "SERIES") "5-146280-1"))
      (libsource (lib "TP_TE_Connectivity_5-146280-1_1POS") (part "TP_TE_Connectivity_5-146280-1_1POS"))
    )
    (comp (ref "TP61")
      (value "TP_TE_Connectivity_5-146280-1_1POS")
      (footprint "TP_TE_Connectivity_5-146280-1_1POS")
      (description "Headers & Wire Housings Unshrouded 1 POS T/H")
      (fields (field (name "SERIES") "5-146280-1"))
      (libsource (lib "TP_TE_Connectivity_5-146280-1_1POS") (part "TP_TE_Connectivity_5-146280-1_1POS"))
    )
    (comp (ref "TP62")
      (value "TP_TE_Connectivity_5-146280-1_1POS")
      (footprint "TP_TE_Connectivity_5-146280-1_1POS")
      (description "Headers & Wire Housings Unshrouded 1 POS T/H")
      (fields (field (name "SERIES") "5-146280-1"))
      (libsource (lib "TP_TE_Connectivity_5-146280-1_1POS") (part "TP_TE_Connectivity_5-146280-1_1POS"))
    )
    (comp (ref "TP63")
      (value "TP_TE_Connectivity_5-146280-1_1POS")
      (footprint "TP_TE_Connectivity_5-146280-1_1POS")
      (description "Headers & Wire Housings Unshrouded 1 POS T/H")
      (fields (field (name "SERIES") "5-146280-1"))
      (libsource (lib "TP_TE_Connectivity_5-146280-1_1POS") (part "TP_TE_Connectivity_5-146280-1_1POS"))
    )
    (comp (ref "TP64")
      (value "TP_TE_Connectivity_5-146280-1_1POS")
      (footprint "TP_TE_Connectivity_5-146280-1_1POS")
      (description "Headers & Wire Housings Unshrouded 1 POS T/H")
      (fields (field (name "SERIES") "5-146280-1"))
      (libsource (lib "TP_TE_Connectivity_5-146280-1_1POS") (part "TP_TE_Connectivity_5-146280-1_1POS"))
    )
    (comp (ref "TP65")
      (value "TP_TE_Connectivity_5-146280-1_1POS")
      (footprint "TP_TE_Connectivity_5-146280-1_1POS")
      (description "Headers & Wire Housings Unshrouded 1 POS T/H")
      (fields (field (name "SERIES") "5-146280-1"))
      (libsource (lib "TP_TE_Connectivity_5-146280-1_1POS") (part "TP_TE_Connectivity_5-146280-1_1POS"))
    )
    (comp (ref "TP66")
      (value "TP_TE_Connectivity_5-146280-1_1POS")
      (footprint "TP_TE_Connectivity_5-146280-1_1POS")
      (description "Headers & Wire Housings Unshrouded 1 POS T/H")
      (fields (field (name "SERIES") "5-146280-1"))
      (libsource (lib "TP_TE_Connectivity_5-146280-1_1POS") (part "TP_TE_Connectivity_5-146280-1_1POS"))
    )
    (comp (ref "TP67")
      (value "TP_TE_Connectivity_5-146280-1_1POS")
      (footprint "TP_TE_Connectivity_5-146280-1_1POS")
      (description "Headers & Wire Housings Unshrouded 1 POS T/H")
      (fields (field (name "SERIES") "5-146280-1"))
      (libsource (lib "TP_TE_Connectivity_5-146280-1_1POS") (part "TP_TE_Connectivity_5-146280-1_1POS"))
    )
    (comp (ref "TP68")
      (value "TP_Keystone_Electronics_5006")
      (footprint "TP_Keystone_Electronics_5006")
      (description "Circuit Board Hardware - PCB TEST POINT BLK .063")
      (fields (field (name "SERIES") "5006"))
      (libsource (lib "TP_Keystone_Electronics_5006") (part "TP_Keystone_Electronics_5006"))
    )
    (comp (ref "TP97")
      (value "TP_TE_Connectivity_5-146280-1_1POS")
      (footprint "TP_TE_Connectivity_5-146280-1_1POS")
      (description "Headers & Wire Housings Unshrouded 1 POS T/H")
      (fields (field (name "SERIES") "5-146280-1"))
      (libsource (lib "TP_TE_Connectivity_5-146280-1_1POS") (part "TP_TE_Connectivity_5-146280-1_1POS"))
    )
    (comp (ref "TP98")
      (value "TP_TE_Connectivity_5-146280-1_1POS")
      (footprint "TP_TE_Connectivity_5-146280-1_1POS")
      (description "Headers & Wire Housings Unshrouded 1 POS T/H")
      (fields (field (name "SERIES") "5-146280-1"))
      (libsource (lib "TP_TE_Connectivity_5-146280-1_1POS") (part "TP_TE_Connectivity_5-146280-1_1POS"))
    )
    (comp (ref "TP99")
      (value "TP_TE_Connectivity_5-146280-1_1POS")
      (footprint "TP_TE_Connectivity_5-146280-1_1POS")
      (description "Headers & Wire Housings Unshrouded 1 POS T/H")
      (fields (field (name "SERIES") "5-146280-1"))
      (libsource (lib "TP_TE_Connectivity_5-146280-1_1POS") (part "TP_TE_Connectivity_5-146280-1_1POS"))
    )
    (comp (ref "TP100")
      (value "TP_TE_Connectivity_5-146280-1_1POS")
      (footprint "TP_TE_Connectivity_5-146280-1_1POS")
      (description "Headers & Wire Housings Unshrouded 1 POS T/H")
      (fields (field (name "SERIES") "5-146280-1"))
      (libsource (lib "TP_TE_Connectivity_5-146280-1_1POS") (part "TP_TE_Connectivity_5-146280-1_1POS"))
    )
    (comp (ref "TP101")
      (value "TP_TE_Connectivity_5-146280-1_1POS")
      (footprint "TP_TE_Connectivity_5-146280-1_1POS")
      (description "Headers & Wire Housings Unshrouded 1 POS T/H")
      (fields (field (name "SERIES") "5-146280-1"))
      (libsource (lib "TP_TE_Connectivity_5-146280-1_1POS") (part "TP_TE_Connectivity_5-146280-1_1POS"))
    )
    (comp (ref "TP102")
      (value "TP_TE_Connectivity_5-146280-1_1POS")
      (footprint "TP_TE_Connectivity_5-146280-1_1POS")
      (description "Headers & Wire Housings Unshrouded 1 POS T/H")
      (fields (field (name "SERIES") "5-146280-1"))
      (libsource (lib "TP_TE_Connectivity_5-146280-1_1POS") (part "TP_TE_Connectivity_5-146280-1_1POS"))
    )
    (comp (ref "U36")
      (value "IC_PSI_DRS4")
      (footprint "DRS4")
      (description "DRS4 QFN76 DAQ Chip")
      (libsource (lib "DRS4_V09") (part "DRS4"))
    )
    (comp (ref "U37")
      (value "INA226AQDGSRQ1")
      (footprint "INA226AQDGSRQ1")
      (libsource (lib "INA226AQDGSRQ1") (part "INA226AQDGSRQ1"))
    )
    (comp (ref "U38")
      (value "INA226AQDGSRQ1")
      (footprint "INA226AQDGSRQ1")
      (libsource (lib "INA226AQDGSRQ1") (part "INA226AQDGSRQ1"))
    )
    (comp (ref "U39")
      (value "TMP112AIDRLR")
      (footprint "TMP112AIDRLR")
      (description "Board Mount Temperature Sensors Hi-Prec Lo-Pwr Dig Temp Sensor")
      (libsource (lib "TMP112AIDRLR") (part "TMP112AIDRLR"))
    )
  )
  (nets
    (net (code "10") (name "/BIAS") (class "Default")
      (node (ref "R108") (pin "1") (pinfunction "1_1") (pintype "passive"))
    )
    (net (code "11") (name "/DRS4_A0") (class "Default")
      (node (ref "R217") (pin "1") (pinfunction "1_1") (pintype "passive"))
      (node (ref "U36") (pin "31") (pinfunction "A0_31") (pintype "input"))
    )
    (net (code "12") (name "/DRS4_A1") (class "Default")
      (node (ref "R218") (pin "1") (pinfunction "1_1") (pintype "passive"))
      (node (ref "U36") (pin "32") (pinfunction "A1_32") (pintype "input"))
    )
    (net (code "13") (name "/DRS4_A2") (class "Default")
      (node (ref "R307") (pin "2") (pinfunction "2_2") (pintype "passive"))
      (node (ref "U36") (pin "60") (pinfunction "A2_60") (pintype "input"))
    )
    (net (code "14") (name "/DRS4_A3") (class "Default")
      (node (ref "R308") (pin "1") (pinfunction "1_1") (pintype "passive"))
      (node (ref "U36") (pin "61") (pinfunction "A3_61") (pintype "input"))
    )
    (net (code "15") (name "/DRS4_AVDD_N") (class "Default")
      (node (ref "R102") (pin "3") (pinfunction "3_3") (pintype "passive"))
      (node (ref "R103") (pin "1") (pinfunction "1_1") (pintype "passive"))
    )
    (net (code "16") (name "/DRS4_AVDD_P") (class "Default")
      (node (ref "R102") (pin "4") (pinfunction "4_4") (pintype "passive"))
      (node (ref "R105") (pin "1") (pinfunction "1_1") (pintype "passive"))
    )
    (net (code "17") (name "/DRS4_DENABLE") (class "Default")
      (node (ref "R113") (pin "2") (pinfunction "2_2") (pintype "passive"))
      (node (ref "R31") (pin "1") (pinfunction "1_1") (pintype "passive"))
      (node (ref "U36") (pin "74") (pinfunction "DENABLE_74") (pintype "input"))
    )
    (net (code "18") (name "/DRS4_DTAP") (class "Default")
      (node (ref "R343") (pin "1") (pinfunction "1_1") (pintype "passive"))
      (node (ref "U36") (pin "62") (pinfunction "DTAP_62") (pintype "output"))
    )
    (net (code "19") (name "/DRS4_DVDD_N") (class "Default")
      (node (ref "R116") (pin "3") (pinfunction "3_3") (pintype "passive"))
      (node (ref "R117") (pin "1") (pinfunction "1_1") (pintype "passive"))
    )
    (net (code "20") (name "/DRS4_DVDD_P") (class "Default")
      (node (ref "R116") (pin "4") (pinfunction "4_4") (pintype "passive"))
      (node (ref "R120") (pin "1") (pinfunction "1_1") (pintype "passive"))
    )
    (net (code "21") (name "/DRS4_DWRITE") (class "Default")
      (node (ref "R114") (pin "2") (pinfunction "2_2") (pintype "passive"))
      (node (ref "R33") (pin "1") (pinfunction "1_1") (pintype "passive"))
      (node (ref "U36") (pin "73") (pinfunction "DWRITE_73") (pintype "input"))
    )
    (net (code "22") (name "/DRS4_IN0_N") (class "Default")
      (node (ref "R168") (pin "2") (pinfunction "2_2") (pintype "passive"))
      (node (ref "U36") (pin "4") (pinfunction "IN0-_4") (pintype "input"))
    )
    (net (code "23") (name "/DRS4_IN0_P") (class "Default")
      (node (ref "R168") (pin "1") (pinfunction "1_1") (pintype "passive"))
      (node (ref "U36") (pin "3") (pinfunction "IN0+_3") (pintype "input"))
    )
    (net (code "24") (name "/DRS4_IN1_N") (class "Default")
      (node (ref "R169") (pin "2") (pinfunction "2_2") (pintype "passive"))
      (node (ref "U36") (pin "6") (pinfunction "IN1-_6") (pintype "input"))
    )
    (net (code "25") (name "/DRS4_IN1_P") (class "Default")
      (node (ref "R169") (pin "1") (pinfunction "1_1") (pintype "passive"))
      (node (ref "U36") (pin "5") (pinfunction "IN1+_5") (pintype "input"))
    )
    (net (code "26") (name "/DRS4_IN2_N") (class "Default")
      (node (ref "R184") (pin "2") (pinfunction "2_2") (pintype "passive"))
      (node (ref "U36") (pin "8") (pinfunction "IN2-_8") (pintype "input"))
    )
    (net (code "27") (name "/DRS4_IN2_P") (class "Default")
      (node (ref "R184") (pin "1") (pinfunction "1_1") (pintype "passive"))
      (node (ref "U36") (pin "7") (pinfunction "IN2+_7") (pintype "input"))
    )
    (net (code "28") (name "/DRS4_IN3_N") (class "Default")
      (node (ref "R185") (pin "2") (pinfunction "2_2") (pintype "passive"))
      (node (ref "U36") (pin "10") (pinfunction "IN3-_10") (pintype "input"))
    )
    (net (code "29") (name "/DRS4_IN3_P") (class "Default")
      (node (ref "R185") (pin "1") (pinfunction "1_1") (pintype "passive"))
      (node (ref "U36") (pin "9") (pinfunction "IN3+_9") (pintype "input"))
    )
    (net (code "30") (name "/DRS4_IN4_N") (class "Default")
      (node (ref "R345") (pin "2") (pinfunction "2_2") (pintype "passive"))
      (node (ref "U36") (pin "12") (pinfunction "IN4-_12") (pintype "input"))
    )
    (net (code "31") (name "/DRS4_IN4_P") (class "Default")
      (node (ref "R345") (pin "1") (pinfunction "1_1") (pintype "passive"))
      (node (ref "U36") (pin "11") (pinfunction "IN4+_11") (pintype "input"))
    )
    (net (code "32") (name "/DRS4_IN5_N") (class "Default")
      (node (ref "R346") (pin "2") (pinfunction "2_2") (pintype "passive"))
      (node (ref "U36") (pin "14") (pinfunction "IN5-_14") (pintype "input"))
    )
    (net (code "33") (name "/DRS4_IN5_P") (class "Default")
      (node (ref "R346") (pin "1") (pinfunction "1_1") (pintype "passive"))
      (node (ref "U36") (pin "13") (pinfunction "IN5+_13") (pintype "input"))
    )
    (net (code "34") (name "/DRS4_IN6_N") (class "Default")
      (node (ref "R347") (pin "2") (pinfunction "2_2") (pintype "passive"))
      (node (ref "U36") (pin "16") (pinfunction "IN6-_16") (pintype "input"))
    )
    (net (code "35") (name "/DRS4_IN6_P") (class "Default")
      (node (ref "R347") (pin "1") (pinfunction "1_1") (pintype "passive"))
      (node (ref "U36") (pin "15") (pinfunction "IN6+_15") (pintype "input"))
    )
    (net (code "36") (name "/DRS4_IN7_N") (class "Default")
      (node (ref "R348") (pin "2") (pinfunction "2_2") (pintype "passive"))
      (node (ref "U36") (pin "18") (pinfunction "IN7-_18") (pintype "input"))
    )
    (net (code "37") (name "/DRS4_IN7_P") (class "Default")
      (node (ref "R348") (pin "1") (pinfunction "1_1") (pintype "passive"))
      (node (ref "U36") (pin "17") (pinfunction "IN7+_17") (pintype "input"))
    )
    (net (code "38") (name "/DRS4_IN8_N") (class "Default")
      (node (ref "R349") (pin "2") (pinfunction "2_2") (pintype "passive"))
      (node (ref "U36") (pin "21") (pinfunction "IN8-_21") (pintype "input"))
    )
    (net (code "39") (name "/DRS4_IN8_P") (class "Default")
      (node (ref "R349") (pin "1") (pinfunction "1_1") (pintype "passive"))
      (node (ref "U36") (pin "20") (pinfunction "IN8+_20") (pintype "input"))
    )
    (net (code "40") (name "/DRS4_OUT8_N") (class "Default")
      (node (ref "U36") (pin "38") (pinfunction "OUT8-_38") (pintype "output"))
    )
    (net (code "41") (name "/DRS4_OUT8_P") (class "Default")
      (node (ref "U36") (pin "37") (pinfunction "OUT8+_37") (pintype "output"))
    )
    (net (code "42") (name "/DRS4_PLLLCK") (class "Default")
      (node (ref "R344") (pin "1") (pinfunction "1_1") (pintype "passive"))
      (node (ref "R362") (pin "1") (pinfunction "1_1") (pintype "passive"))
    )
    (net (code "43") (name "/DRS4_RSRLOAD") (class "Default")
      (node (ref "R163") (pin "1") (pinfunction "1_1") (pintype "passive"))
      (node (ref "U36") (pin "29") (pinfunction "RSRLOAD_29") (pintype "input"))
    )
    (net (code "44") (name "/DRS4_SRCLK") (class "Default")
      (node (ref "R115") (pin "1") (pinfunction "1_1") (pintype "passive"))
      (node (ref "R312") (pin "1") (pinfunction "1_1") (pintype "passive"))
      (node (ref "U36") (pin "28") (pinfunction "SRCLK_28") (pintype "input"))
    )
    (net (code "45") (name "/DRS4_SRIN") (class "Default")
      (node (ref "R315") (pin "1") (pinfunction "1_1") (pintype "passive"))
      (node (ref "U36") (pin "27") (pinfunction "SRIN_27") (pintype "input"))
    )
    (net (code "46") (name "/DRS4_SROUT") (class "Default")
      (node (ref "R179") (pin "1") (pinfunction "1_1") (pintype "passive"))
      (node (ref "U36") (pin "26") (pinfunction "SROUT_26") (pintype "output"))
    )
    (net (code "47") (name "/DRS4_WSRIN") (class "Default")
      (node (ref "R59") (pin "1") (pinfunction "1_1") (pintype "passive"))
      (node (ref "U36") (pin "75") (pinfunction "WSRIN_75") (pintype "input"))
    )
    (net (code "48") (name "/DRS4_WSROUT") (class "Default")
      (node (ref "R60") (pin "1") (pinfunction "1_1") (pintype "passive"))
      (node (ref "U36") (pin "25") (pinfunction "WSROUT_25") (pintype "output"))
    )
    (net (code "49") (name "/DRS4~{_RESET}") (class "Default")
      (node (ref "R35") (pin "1") (pinfunction "1_1") (pintype "passive"))
      (node (ref "U36") (pin "35") (pinfunction "~{RESET}_35") (pintype "input"))
    )
    (net (code "50") (name "/O-OFS") (class "Default")
      (node (ref "R109") (pin "1") (pinfunction "1_1") (pintype "passive"))
      (node (ref "R110") (pin "1") (pinfunction "1_1") (pintype "passive"))
      (node (ref "R57") (pin "1") (pinfunction "1_1") (pintype "passive"))
      (node (ref "U36") (pin "36") (pinfunction "O-OFS_36") (pintype "input"))
    )
    (net (code "51") (name "/R-OFS") (class "Default")
      (node (ref "C142") (pin "1") (pinfunction "1_1") (pintype "passive"))
      (node (ref "C143") (pin "2") (pinfunction "2_2") (pintype "passive"))
      (node (ref "C144") (pin "2") (pinfunction "2_2") (pintype "passive"))
      (node (ref "R58") (pin "1") (pinfunction "1_1") (pintype "passive"))
      (node (ref "U36") (pin "30") (pinfunction "ROFS_30") (pintype "input"))
    )
    (net (code "52") (name "/REFCLK+") (class "Default")
      (node (ref "R106") (pin "1") (pinfunction "1_1") (pintype "passive"))
      (node (ref "U36") (pin "66") (pinfunction "REFCLK+_66") (pintype "input"))
    )
    (net (code "53") (name "/REFCLK-") (class "Default")
      (node (ref "R106") (pin "2") (pinfunction "2_2") (pintype "passive"))
      (node (ref "U36") (pin "67") (pinfunction "REFCLK-_67") (pintype "input"))
    )
    (net (code "54") (name "/SCL_DRS4INA226") (class "Default")
      (node (ref "U38") (pin "1") (pinfunction "A1_1") (pintype "input"))
      (node (ref "U38") (pin "5") (pinfunction "SCL_5") (pintype "input"))
    )
    (net (code "55") (name "/SCL_DRS4INA226_AVDD") (class "Default")
      (node (ref "U37") (pin "5") (pinfunction "SCL_5") (pintype "input"))
    )
    (net (code "56") (name "/SCL_DRS4TMP112") (class "Default")
      (node (ref "U39") (pin "1") (pinfunction "SCL_1") (pintype "input"))
    )
    (net (code "57") (name "/SDA_DRS4INA226") (class "Default")
      (node (ref "U38") (pin "2") (pinfunction "A0_2") (pintype "input"))
      (node (ref "U38") (pin "4") (pinfunction "SDA_4") (pintype "bidirectional"))
    )
    (net (code "58") (name "/SDA_DRS4INA226_AVDD") (class "Default")
      (node (ref "U37") (pin "4") (pinfunction "SDA_4") (pintype "bidirectional"))
    )
    (net (code "59") (name "/SDA_DRS4TMP112") (class "Default")
      (node (ref "U39") (pin "6") (pinfunction "SDA_6") (pintype "bidirectional"))
    )
    (net (code "67") (name "2V5_DRS_ANA") (class "Default")
      (node (ref "R102") (pin "1") (pinfunction "1_1") (pintype "passive"))
      (node (ref "U37") (pin "8") (pinfunction "VBUS_8") (pintype "input"))
    )
    (net (code "68") (name "3.3V") (class "Default")
      (node (ref "C136") (pin "2") (pinfunction "2_2") (pintype "passive"))
      (node (ref "C137") (pin "2") (pinfunction "2_2") (pintype "passive"))
      (node (ref "C146") (pin "2") (pinfunction "2_2") (pintype "passive"))
      (node (ref "C147") (pin "2") (pinfunction "2_2") (pintype "passive"))
      (node (ref "C148") (pin "2") (pinfunction "2_2") (pintype "passive"))
      (node (ref "C149") (pin "2") (pinfunction "2_2") (pintype "passive"))
      (node (ref "Q13") (pin "2") (pinfunction "E_2") (pintype "passive"))
      (node (ref "Q14") (pin "2") (pinfunction "E_2") (pintype "passive"))
      (node (ref "Q15") (pin "2") (pinfunction "E_2") (pintype "passive"))
      (node (ref "R104") (pin "2") (pinfunction "2_2") (pintype "passive"))
      (node (ref "R116") (pin "1") (pinfunction "1_1") (pintype "passive"))
      (node (ref "R118") (pin "2") (pinfunction "2_2") (pintype "passive"))
      (node (ref "R119") (pin "2") (pinfunction "2_2") (pintype "passive"))
      (node (ref "U37") (pin "6") (pinfunction "VS+_6") (pintype "input"))
      (node (ref "U38") (pin "6") (pinfunction "VS+_6") (pintype "input"))
      (node (ref "U39") (pin "5") (pinfunction "V+_5") (pintype "power_in"))
    )
    (net (code "69") (name "DRS4_2V5_ADM") (class "Default")
      (node (ref "J4") (pin "2") (pinfunction "2_2") (pintype "passive"))
    )
    (net (code "70") (name "DRS4_2V5_MIC") (class "Default")
      (node (ref "J5") (pin "2") (pinfunction "2_2") (pintype "passive"))
    )
    (net (code "71") (name "DRS4_2V5_TPS") (class "Default")
      (node (ref "J3") (pin "2") (pinfunction "2_2") (pintype "passive"))
    )
    (net (code "72") (name "DRS4_AVDD") (class "Default")
      (node (ref "C150") (pin "1") (pinfunction "1_1") (pintype "passive"))
      (node (ref "C151") (pin "2") (pinfunction "2_2") (pintype "passive"))
      (node (ref "C152") (pin "1") (pinfunction "1_1") (pintype "passive"))
      (node (ref "C153") (pin "1") (pinfunction "1_1") (pintype "passive"))
      (node (ref "C154") (pin "1") (pinfunction "1_1") (pintype "passive"))
      (node (ref "C155") (pin "2") (pinfunction "2_2") (pintype "passive"))
      (node (ref "C156") (pin "2") (pinfunction "2_2") (pintype "passive"))
      (node (ref "C157") (pin "2") (pinfunction "2_2") (pintype "passive"))
      (node (ref "C158") (pin "2") (pinfunction "2_2") (pintype "passive"))
      (node (ref "C159") (pin "2") (pinfunction "2_2") (pintype "passive"))
      (node (ref "R102") (pin "2") (pinfunction "2_2") (pintype "passive"))
      (node (ref "U36") (pin "59") (pinfunction "AVDD_59") (pintype "power_in"))
      (node (ref "U36") (pin "65") (pinfunction "AVDD_65") (pintype "power_in"))
      (node (ref "U36") (pin "71") (pinfunction "AVDD_71") (pintype "power_in"))
      (node (ref "U36") (pin "76") (pinfunction "AVDD_76") (pintype "power_in"))
    )
    (net (code "73") (name "DRS4_DVDD") (class "Default")
      (node (ref "C1") (pin "1") (pinfunction "1_1") (pintype "passive"))
      (node (ref "C110") (pin "1") (pinfunction "1_1") (pintype "passive"))
      (node (ref "C160") (pin "1") (pinfunction "1_1") (pintype "passive"))
      (node (ref "C161") (pin "2") (pinfunction "2_2") (pintype "passive"))
      (node (ref "C162") (pin "2") (pinfunction "2_2") (pintype "passive"))
      (node (ref "C163") (pin "2") (pinfunction "2_2") (pintype "passive"))
      (node (ref "C164") (pin "2") (pinfunction "2_2") (pintype "passive"))
      (node (ref "C165") (pin "2") (pinfunction "2_2") (pintype "passive"))
      (node (ref "C166") (pin "2") (pinfunction "2_2") (pintype "passive"))
      (node (ref "C167") (pin "1") (pinfunction "1_1") (pintype "passive"))
      (node (ref "C168") (pin "1") (pinfunction "1_1") (pintype "passive"))
      (node (ref "C2") (pin "1") (pinfunction "1_1") (pintype "passive"))
      (node (ref "C3") (pin "1") (pinfunction "1_1") (pintype "passive"))
      (node (ref "C66") (pin "1") (pinfunction "1_1") (pintype "passive"))
      (node (ref "FB9") (pin "1") (pinfunction "1_1") (pintype "passive"))
      (node (ref "U36") (pin "23") (pinfunction "DVDD_23") (pintype "power_in"))
      (node (ref "U36") (pin "24") (pinfunction "DVDD_24") (pintype "power_in"))
      (node (ref "U36") (pin "33") (pinfunction "DVDD_33") (pintype "power_in"))
      (node (ref "U36") (pin "34") (pinfunction "DVDD_34") (pintype "power_in"))
      (node (ref "U38") (pin "8") (pinfunction "VBUS_8") (pintype "input"))
    )
    (net (code "74") (name "Net-(C138-Pad2)") (class "Default")
      (node (ref "C138") (pin "2") (pinfunction "2_2") (pintype "passive"))
      (node (ref "FB9") (pin "2") (pinfunction "2_2") (pintype "passive"))
      (node (ref "R109") (pin "2") (pinfunction "2_2") (pintype "passive"))
    )
    (net (code "75") (name "Net-(C139-Pad2)") (class "Default")
      (node (ref "C139") (pin "2") (pinfunction "2_2") (pintype "passive"))
      (node (ref "R111") (pin "1") (pinfunction "1_1") (pintype "passive"))
    )
    (net (code "76") (name "Net-(C141-Pad2)") (class "Default")
      (node (ref "C141") (pin "2") (pinfunction "2_2") (pintype "passive"))
      (node (ref "R115") (pin "2") (pinfunction "2_2") (pintype "passive"))
    )
    (net (code "77") (name "Net-(D24-A)") (class "Default")
      (node (ref "D24") (pin "2") (pinfunction "A_2") (pintype "passive"))
      (node (ref "Q13") (pin "3") (pinfunction "C_3") (pintype "passive"))
    )
    (net (code "78") (name "Net-(D24-K)") (class "Default")
      (node (ref "D24") (pin "1") (pinfunction "K_1") (pintype "passive"))
      (node (ref "R112") (pin "2") (pinfunction "2_2") (pintype "passive"))
    )
    (net (code "79") (name "Net-(D25-A)") (class "Default")
      (node (ref "D25") (pin "2") (pinfunction "A_2") (pintype "passive"))
      (node (ref "Q14") (pin "3") (pinfunction "C_3") (pintype "passive"))
    )
    (net (code "80") (name "Net-(D25-K)") (class "Default")
      (node (ref "D25") (pin "1") (pinfunction "K_1") (pintype "passive"))
      (node (ref "R123") (pin "2") (pinfunction "2_2") (pintype "passive"))
    )
    (net (code "81") (name "Net-(D26-A)") (class "Default")
      (node (ref "D26") (pin "2") (pinfunction "A_2") (pintype "passive"))
      (node (ref "Q15") (pin "3") (pinfunction "C_3") (pintype "passive"))
    )
    (net (code "82") (name "Net-(D26-K)") (class "Default")
      (node (ref "D26") (pin "1") (pinfunction "K_1") (pintype "passive"))
      (node (ref "R124") (pin "2") (pinfunction "2_2") (pintype "passive"))
    )
    (net (code "83") (name "Net-(J3-Pad1)") (class "Default")
      (node (ref "J3") (pin "1") (pinfunction "1_1") (pintype "passive"))
      (node (ref "J4") (pin "1") (pinfunction "1_1") (pintype "passive"))
      (node (ref "J5") (pin "1") (pinfunction "1_1") (pintype "passive"))
      (node (ref "R116") (pin "2") (pinfunction "2_2") (pintype "passive"))
    )
    (net (code "84") (name "Net-(Q13-B)") (class "Default")
      (node (ref "Q13") (pin "1") (pinfunction "B_1") (pintype "passive"))
      (node (ref "R104") (pin "1") (pinfunction "1_1") (pintype "passive"))
      (node (ref "R107") (pin "1") (pinfunction "1_1") (pintype "passive"))
    )
    (net (code "85") (name "Net-(Q14-B)") (class "Default")
      (node (ref "Q14") (pin "1") (pinfunction "B_1") (pintype "passive"))
      (node (ref "R119") (pin "1") (pinfunction "1_1") (pintype "passive"))
      (node (ref "R122") (pin "1") (pinfunction "1_1") (pintype "passive"))
    )
    (net (code "86") (name "Net-(Q15-B)") (class "Default")
      (node (ref "Q15") (pin "1") (pinfunction "B_1") (pintype "passive"))
      (node (ref "R118") (pin "1") (pinfunction "1_1") (pintype "passive"))
      (node (ref "R121") (pin "1") (pinfunction "1_1") (pintype "passive"))
    )
    (net (code "87") (name "Net-(R31-Pad2)") (class "Default")
      (node (ref "R31") (pin "2") (pinfunction "2_2") (pintype "passive"))
      (node (ref "TP59") (pin "1") (pinfunction "1_1") (pintype "input"))
    )
    (net (code "88") (name "Net-(R33-Pad2)") (class "Default")
      (node (ref "R33") (pin "2") (pinfunction "2_2") (pintype "passive"))
      (node (ref "TP60") (pin "1") (pinfunction "1_1") (pintype "input"))
    )
    (net (code "89") (name "Net-(R35-Pad2)") (class "Default")
      (node (ref "R35") (pin "2") (pinfunction "2_2") (pintype "passive"))
      (node (ref "TP61") (pin "1") (pinfunction "1_1") (pintype "input"))
    )
    (net (code "90") (name "Net-(R57-Pad2)") (class "Default")
      (node (ref "R57") (pin "2") (pinfunction "2_2") (pintype "passive"))
      (node (ref "TP62") (pin "1") (pinfunction "1_1") (pintype "input"))
    )
    (net (code "91") (name "Net-(R58-Pad2)") (class "Default")
      (node (ref "R58") (pin "2") (pinfunction "2_2") (pintype "passive"))
      (node (ref "TP63") (pin "1") (pinfunction "1_1") (pintype "input"))
    )
    (net (code "92") (name "Net-(R59-Pad2)") (class "Default")
      (node (ref "R59") (pin "2") (pinfunction "2_2") (pintype "passive"))
      (node (ref "TP97") (pin "1") (pinfunction "1_1") (pintype "input"))
    )
    (net (code "93") (name "Net-(R60-Pad2)") (class "Default")
      (node (ref "R60") (pin "2") (pinfunction "2_2") (pintype "passive"))
      (node (ref "TP98") (pin "1") (pinfunction "1_1") (pintype "input"))
    )
    (net (code "94") (name "Net-(R163-Pad2)") (class "Default")
      (node (ref "R163") (pin "2") (pinfunction "2_2") (pintype "passive"))
      (node (ref "TP99") (pin "1") (pinfunction "1_1") (pintype "input"))
    )
    (net (code "95") (name "Net-(R179-Pad2)") (class "Default")
      (node (ref "R179") (pin "2") (pinfunction "2_2") (pintype "passive"))
      (node (ref "TP100") (pin "1") (pinfunction "1_1") (pintype "input"))
    )
    (net (code "96") (name "Net-(R217-Pad2)") (class "Default")
      (node (ref "R217") (pin "2") (pinfunction "2_2") (pintype "passive"))
      (node (ref "TP64") (pin "1") (pinfunction "1_1") (pintype "input"))
    )
    (net (code "97") (name "Net-(R218-Pad2)") (class "Default")
      (node (ref "R218") (pin "2") (pinfunction "2_2") (pintype "passive"))
      (node (ref "TP65") (pin "1") (pinfunction "1_1") (pintype "input"))
    )
    (net (code "98") (name "Net-(R307-Pad1)") (class "Default")
      (node (ref "R307") (pin "1") (pinfunction "1_1") (pintype "passive"))
      (node (ref "TP66") (pin "1") (pinfunction "1_1") (pintype "input"))
    )
    (net (code "99") (name "Net-(R308-Pad2)") (class "Default")
      (node (ref "R308") (pin "2") (pinfunction "2_2") (pintype "passive"))
      (node (ref "TP67") (pin "1") (pinfunction "1_1") (pintype "input"))
    )
    (net (code "100") (name "Net-(R312-Pad2)") (class "Default")
      (node (ref "R312") (pin "2") (pinfunction "2_2") (pintype "passive"))
      (node (ref "TP101") (pin "1") (pinfunction "1_1") (pintype "input"))
    )
    (net (code "101") (name "Net-(R315-Pad2)") (class "Default")
      (node (ref "R315") (pin "2") (pinfunction "2_2") (pintype "passive"))
      (node (ref "TP102") (pin "1") (pinfunction "1_1") (pintype "input"))
    )
    (net (code "102") (name "Net-(R343-Pad2)") (class "Default")
      (node (ref "R343") (pin "2") (pinfunction "2_2") (pintype "passive"))
      (node (ref "TP57") (pin "1") (pinfunction "1_1") (pintype "input"))
    )
    (net (code "103") (name "Net-(R344-Pad2)") (class "Default")
      (node (ref "R344") (pin "2") (pinfunction "2_2") (pintype "passive"))
      (node (ref "TP58") (pin "1") (pinfunction "1_1") (pintype "input"))
    )
    (net (code "104") (name "Net-(U36-BIAS)") (class "Default")
      (node (ref "R108") (pin "2") (pinfunction "2_2") (pintype "passive"))
      (node (ref "U36") (pin "72") (pinfunction "BIAS_72") (pintype "input"))
    )
    (net (code "105") (name "Net-(U36-DSPEED)") (class "Default")
      (node (ref "C140") (pin "2") (pinfunction "2_2") (pintype "passive"))
      (node (ref "R111") (pin "2") (pinfunction "2_2") (pintype "passive"))
      (node (ref "U36") (pin "68") (pinfunction "PLLOUT_68") (pintype "output"))
      (node (ref "U36") (pin "69") (pinfunction "DSPEED_69") (pintype "input"))
    )
    (net (code "106") (name "Net-(U36-PLLLOCK)") (class "Default")
      (node (ref "C126") (pin "1") (pinfunction "1_1") (pintype "passive"))
      (node (ref "R362") (pin "2") (pinfunction "2_2") (pintype "passive"))
      (node (ref "U36") (pin "63") (pinfunction "PLLLOCK_63") (pintype "output"))
    )
    (net (code "107") (name "Net-(U37-ALERT)") (class "Default")
      (node (ref "R107") (pin "2") (pinfunction "2_2") (pintype "passive"))
      (node (ref "U37") (pin "3") (pinfunction "ALERT_3") (pintype "open_collector"))
    )
    (net (code "108") (name "Net-(U37-VIN+)") (class "Default")
      (node (ref "C135") (pin "1") (pinfunction "1_1") (pintype "passive"))
      (node (ref "R105") (pin "2") (pinfunction "2_2") (pintype "passive"))
      (node (ref "U37") (pin "10") (pinfunction "VIN+_10") (pintype "input"))
    )
    (net (code "109") (name "Net-(U37-VIN-)") (class "Default")
      (node (ref "C135") (pin "2") (pinfunction "2_2") (pintype "passive"))
      (node (ref "R103") (pin "2") (pinfunction "2_2") (pintype "passive"))
      (node (ref "U37") (pin "9") (pinfunction "VIN-_9") (pintype "input"))
    )
    (net (code "110") (name "Net-(U38-ALERT)") (class "Default")
      (node (ref "R121") (pin "2") (pinfunction "2_2") (pintype "passive"))
      (node (ref "U38") (pin "3") (pinfunction "ALERT_3") (pintype "open_collector"))
    )
    (net (code "111") (name "Net-(U38-VIN+)") (class "Default")
      (node (ref "C145") (pin "1") (pinfunction "1_1") (pintype "passive"))
      (node (ref "R120") (pin "2") (pinfunction "2_2") (pintype "passive"))
      (node (ref "U38") (pin "10") (pinfunction "VIN+_10") (pintype "input"))
    )
    (net (code "112") (name "Net-(U38-VIN-)") (class "Default")
      (node (ref "C145") (pin "2") (pinfunction "2_2") (pintype "passive"))
      (node (ref "R117") (pin "2") (pinfunction "2_2") (pintype "passive"))
      (node (ref "U38") (pin "9") (pinfunction "VIN-_9") (pintype "input"))
    )
    (net (code "113") (name "Net-(U39-ALERT)") (class "Default")
      (node (ref "R122") (pin "2") (pinfunction "2_2") (pintype "passive"))
      (node (ref "U39") (pin "3") (pinfunction "ALERT_3") (pintype "open_collector"))
    )
    (net (code "114") (name "TRB_GND") (class "Default")
      (node (ref "C1") (pin "2") (pinfunction "2_2") (pintype "passive"))
      (node (ref "C110") (pin "2") (pinfunction "2_2") (pintype "passive"))
      (node (ref "C126") (pin "2") (pinfunction "2_2") (pintype "passive"))
      (node (ref "C136") (pin "1") (pinfunction "1_1") (pintype "passive"))
      (node (ref "C137") (pin "1") (pinfunction "1_1") (pintype "passive"))
      (node (ref "C138") (pin "1") (pinfunction "1_1") (pintype "passive"))
      (node (ref "C139") (pin "1") (pinfunction "1_1") (pintype "passive"))
      (node (ref "C140") (pin "1") (pinfunction "1_1") (pintype "passive"))
      (node (ref "C141") (pin "1") (pinfunction "1_1") (pintype "passive"))
      (node (ref "C142") (pin "2") (pinfunction "2_2") (pintype "passive"))
      (node (ref "C143") (pin "1") (pinfunction "1_1") (pintype "passive"))
      (node (ref "C144") (pin "1") (pinfunction "1_1") (pintype "passive"))
      (node (ref "C146") (pin "1") (pinfunction "1_1") (pintype "passive"))
      (node (ref "C147") (pin "1") (pinfunction "1_1") (pintype "passive"))
      (node (ref "C148") (pin "1") (pinfunction "1_1") (pintype "passive"))
      (node (ref "C149") (pin "1") (pinfunction "1_1") (pintype "passive"))
      (node (ref "C150") (pin "2") (pinfunction "2_2") (pintype "passive"))
      (node (ref "C151") (pin "1") (pinfunction "1_1") (pintype "passive"))
      (node (ref "C152") (pin "2") (pinfunction "2_2") (pintype "passive"))
      (node (ref "C153") (pin "2") (pinfunction "2_2") (pintype "passive"))
      (node (ref "C154") (pin "2") (pinfunction "2_2") (pintype "passive"))
      (node (ref "C155") (pin "1") (pinfunction "1_1") (pintype "passive"))
      (node (ref "C156") (pin "1") (pinfunction "1_1") (pintype "passive"))
      (node (ref "C157") (pin "1") (pinfunction "1_1") (pintype "passive"))
      (node (ref "C158") (pin "1") (pinfunction "1_1") (pintype "passive"))
      (node (ref "C159") (pin "1") (pinfunction "1_1") (pintype "passive"))
      (node (ref "C160") (pin "2") (pinfunction "2_2") (pintype "passive"))
      (node (ref "C161") (pin "1") (pinfunction "1_1") (pintype "passive"))
      (node (ref "C162") (pin "1") (pinfunction "1_1") (pintype "passive"))
      (node (ref "C163") (pin "1") (pinfunction "1_1") (pintype "passive"))
      (node (ref "C164") (pin "1") (pinfunction "1_1") (pintype "passive"))
      (node (ref "C165") (pin "1") (pinfunction "1_1") (pintype "passive"))
      (node (ref "C166") (pin "1") (pinfunction "1_1") (pintype "passive"))
      (node (ref "C167") (pin "2") (pinfunction "2_2") (pintype "passive"))
      (node (ref "C168") (pin "2") (pinfunction "2_2") (pintype "passive"))
      (node (ref "C2") (pin "2") (pinfunction "2_2") (pintype "passive"))
      (node (ref "C3") (pin "2") (pinfunction "2_2") (pintype "passive"))
      (node (ref "C66") (pin "2") (pinfunction "2_2") (pintype "passive"))
      (node (ref "R110") (pin "2") (pinfunction "2_2") (pintype "passive"))
      (node (ref "R112") (pin "1") (pinfunction "1_1") (pintype "passive"))
      (node (ref "R113") (pin "1") (pinfunction "1_1") (pintype "passive"))
      (node (ref "R114") (pin "1") (pinfunction "1_1") (pintype "passive"))
      (node (ref "R123") (pin "1") (pinfunction "1_1") (pintype "passive"))
      (node (ref "R124") (pin "1") (pinfunction "1_1") (pintype "passive"))
      (node (ref "TP18") (pin "1") (pinfunction "1_1") (pintype "input"))
      (node (ref "TP38") (pin "1") (pinfunction "1_1") (pintype "input"))
      (node (ref "TP39") (pin "1") (pinfunction "1_1") (pintype "input"))
      (node (ref "TP42") (pin "1") (pinfunction "1_1") (pintype "input"))
      (node (ref "TP43") (pin "1") (pinfunction "1_1") (pintype "input"))
      (node (ref "TP44") (pin "1") (pinfunction "1_1") (pintype "input"))
      (node (ref "TP68") (pin "1") (pinfunction "1_1") (pintype "input"))
      (node (ref "U36") (pin "1") (pinfunction "AGND_1") (pintype "passive"))
      (node (ref "U36") (pin "19") (pinfunction "DGND_19") (pintype "passive"))
      (node (ref "U36") (pin "2") (pinfunction "AGND_2") (pintype "passive"))
      (node (ref "U36") (pin "22") (pinfunction "DGND_22") (pintype "passive"))
      (node (ref "U36") (pin "39") (pinfunction "DGND_39") (pintype "passive"))
      (node (ref "U36") (pin "44") (pinfunction "DGND_44") (pintype "passive"))
      (node (ref "U36") (pin "53") (pinfunction "DGND_53") (pintype "passive"))
      (node (ref "U36") (pin "58") (pinfunction "AGND_58") (pintype "passive"))
      (node (ref "U36") (pin "64") (pinfunction "AGND_64") (pintype "passive"))
      (node (ref "U36") (pin "70") (pinfunction "AGND_70") (pintype "passive"))
      (node (ref "U36") (pin "77") (pinfunction "PAD_77") (pintype "passive"))
      (node (ref "U37") (pin "1") (pinfunction "A1_1") (pintype "input"))
      (node (ref "U37") (pin "2") (pinfunction "A0_2") (pintype "input"))
      (node (ref "U37") (pin "7") (pinfunction "GND_7") (pintype "power_in"))
      (node (ref "U38") (pin "7") (pinfunction "GND_7") (pintype "power_in"))
      (node (ref "U39") (pin "2") (pinfunction "GND_2") (pintype "power_in"))
      (node (ref "U39") (pin "4") (pinfunction "ADD0_4") (pintype "input"))
    )
    (net (code "115") (name "unconnected-(U36-OUT0+-Pad57)") (class "Default")
      (node (ref "U36") (pin "57") (pinfunction "OUT0+_57") (pintype "output+no_connect"))
    )
    (net (code "116") (name "unconnected-(U36-OUT0--Pad56)") (class "Default")
      (node (ref "U36") (pin "56") (pinfunction "OUT0-_56") (pintype "output+no_connect"))
    )
    (net (code "117") (name "unconnected-(U36-OUT1+-Pad54)") (class "Default")
      (node (ref "U36") (pin "54") (pinfunction "OUT1+_54") (pintype "output+no_connect"))
    )
    (net (code "118") (name "unconnected-(U36-OUT1--Pad55)") (class "Default")
      (node (ref "U36") (pin "55") (pinfunction "OUT1-_55") (pintype "output+no_connect"))
    )
    (net (code "119") (name "unconnected-(U36-OUT2+-Pad52)") (class "Default")
      (node (ref "U36") (pin "52") (pinfunction "OUT2+_52") (pintype "output+no_connect"))
    )
    (net (code "120") (name "unconnected-(U36-OUT2--Pad51)") (class "Default")
      (node (ref "U36") (pin "51") (pinfunction "OUT2-_51") (pintype "output+no_connect"))
    )
    (net (code "121") (name "unconnected-(U36-OUT3+-Pad49)") (class "Default")
      (node (ref "U36") (pin "49") (pinfunction "OUT3+_49") (pintype "output+no_connect"))
    )
    (net (code "122") (name "unconnected-(U36-OUT3--Pad50)") (class "Default")
      (node (ref "U36") (pin "50") (pinfunction "OUT3-_50") (pintype "output+no_connect"))
    )
    (net (code "123") (name "unconnected-(U36-OUT4+-Pad48)") (class "Default")
      (node (ref "U36") (pin "48") (pinfunction "OUT4+_48") (pintype "output+no_connect"))
    )
    (net (code "124") (name "unconnected-(U36-OUT4--Pad47)") (class "Default")
      (node (ref "U36") (pin "47") (pinfunction "OUT4-_47") (pintype "output+no_connect"))
    )
    (net (code "125") (name "unconnected-(U36-OUT5+-Pad45)") (class "Default")
      (node (ref "U36") (pin "45") (pinfunction "OUT5+_45") (pintype "output+no_connect"))
    )
    (net (code "126") (name "unconnected-(U36-OUT5--Pad46)") (class "Default")
      (node (ref "U36") (pin "46") (pinfunction "OUT5-_46") (pintype "output+no_connect"))
    )
    (net (code "127") (name "unconnected-(U36-OUT6+-Pad42)") (class "Default")
      (node (ref "U36") (pin "42") (pinfunction "OUT6+_42") (pintype "output+no_connect"))
    )
    (net (code "128") (name "unconnected-(U36-OUT6--Pad43)") (class "Default")
      (node (ref "U36") (pin "43") (pinfunction "OUT6-_43") (pintype "output+no_connect"))
    )
    (net (code "129") (name "unconnected-(U36-OUT7+-Pad40)") (class "Default")
      (node (ref "U36") (pin "40") (pinfunction "OUT7+_40") (pintype "output+no_connect"))
    )
    (net (code "130") (name "unconnected-(U36-OUT7--Pad41)") (class "Default")
      (node (ref "U36") (pin "41") (pinfunction "OUT7-_41") (pintype "output+no_connect"))
    )
  )
)
